# Speccy2007_128K_Ljubitel.net
KiCad netlist of a schematic drawn in EAGLE
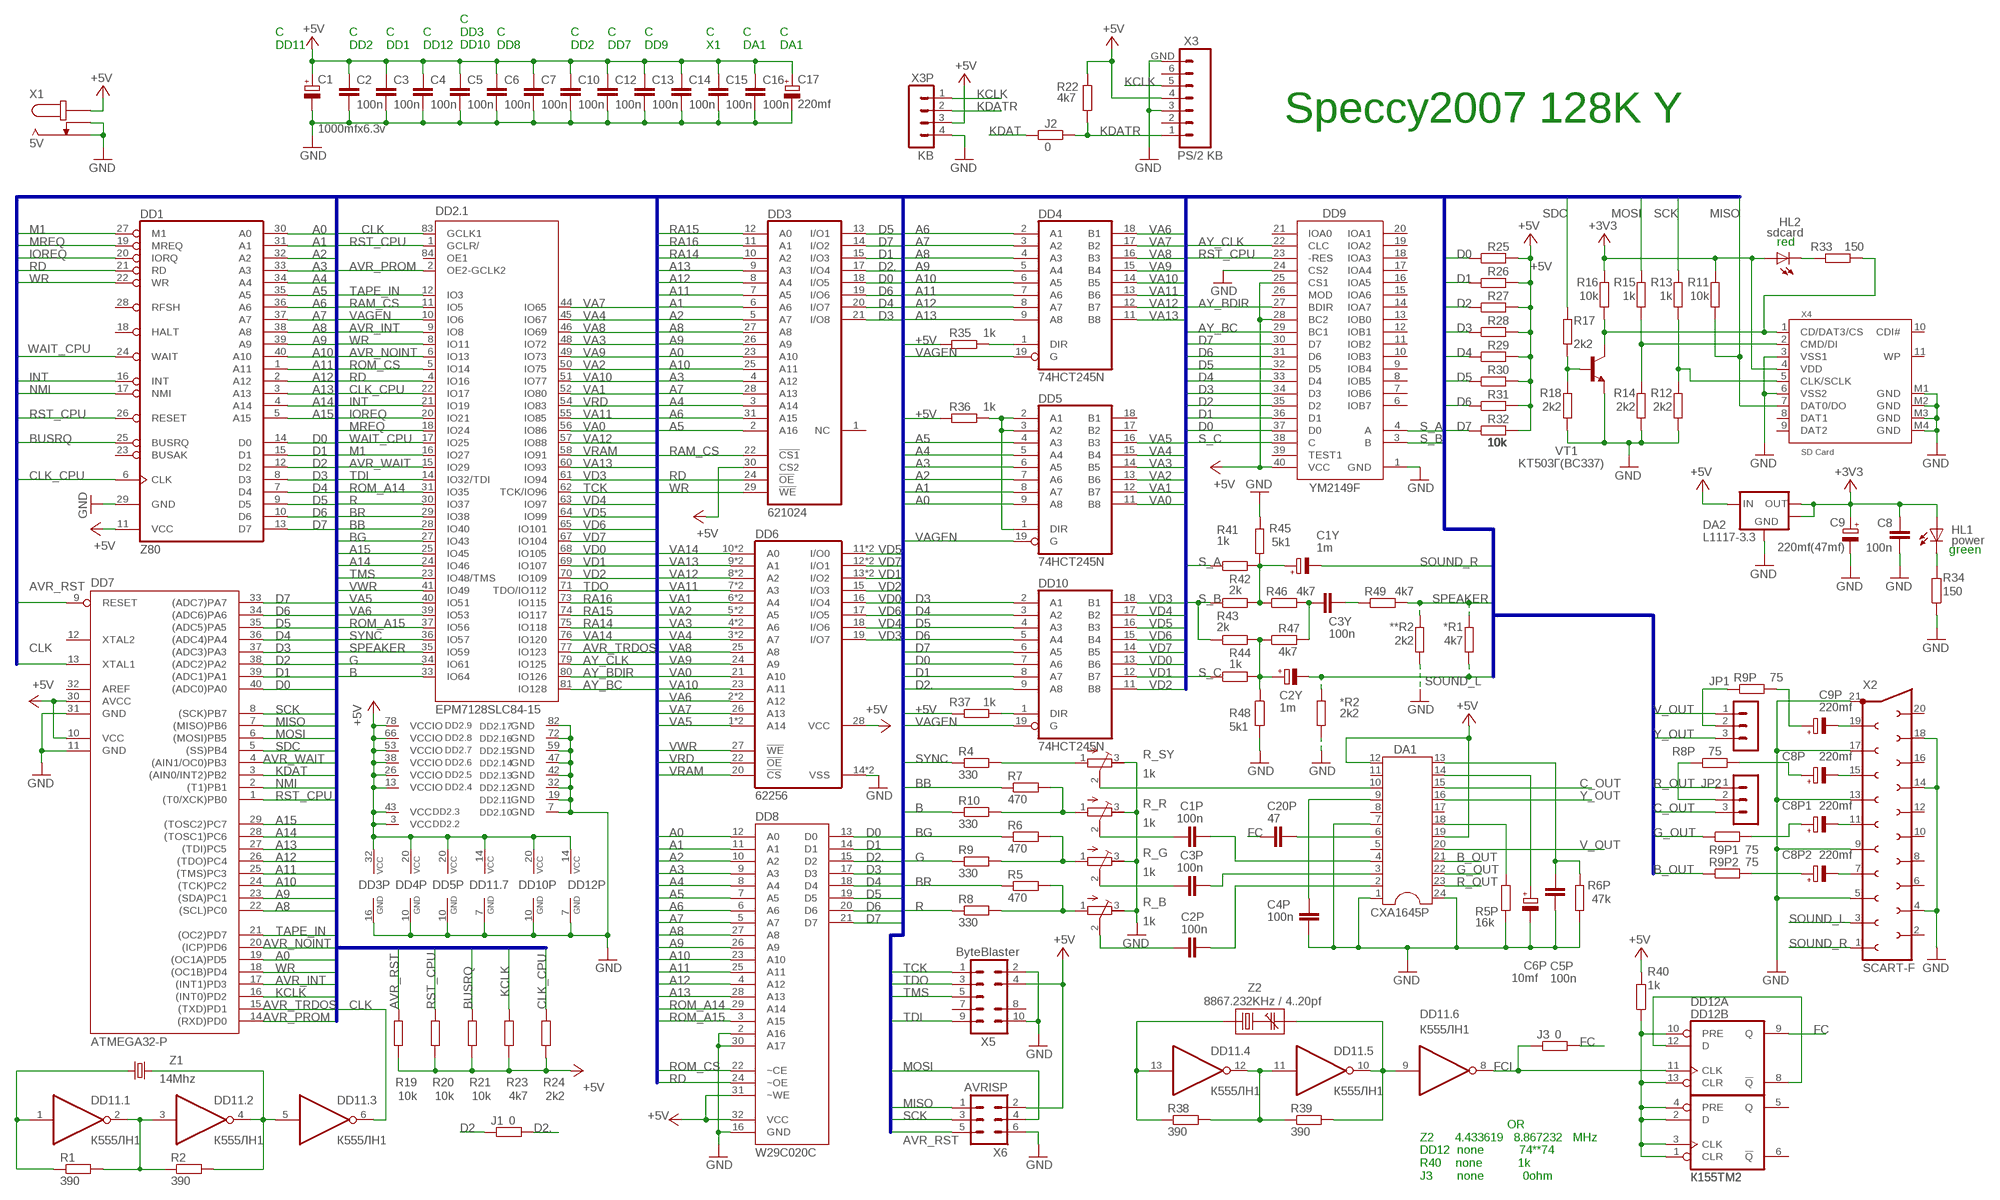
[diagram p0: schematic, sheet 1]

(export (version "E")
  (design (tool "Eeschema 10.0.6"))
  (components
    (comp (ref "**R2")
      (value "2k2")
      (footprint "eagle-import:R1206")
      (libsource (lib "eagle-import") (part "rcl_R-EU_R1206"))
    )
    (comp (ref "*R1")
      (value "4k7")
      (footprint "eagle-import:R0805")
      (libsource (lib "eagle-import") (part "rcl_R-EU_R0805"))
    )
    (comp (ref "*R2")
      (value "2k2")
      (footprint "eagle-import:R0805")
      (libsource (lib "eagle-import") (part "rcl_R-EU_R0805"))
    )
    (comp (ref "C1")
      (value "1000mfx6.3v")
      (footprint "eagle-import:E3,5-8")
      (libsource (lib "eagle-import") (part "CPOL-EUE3.5-8"))
    )
    (comp (ref "C1P")
      (value "100n")
      (footprint "eagle-import:C0805")
      (libsource (lib "eagle-import") (part "C-EUC0805"))
    )
    (comp (ref "C1Y")
      (value "1m")
      (footprint "eagle-import:E2,5-5")
      (libsource (lib "eagle-import") (part "CPOL-EUE2.5-5"))
    )
    (comp (ref "C2")
      (value "100n")
      (footprint "eagle-import:C0805")
      (libsource (lib "eagle-import") (part "C-EUC0805"))
    )
    (comp (ref "C2P")
      (value "100n")
      (footprint "eagle-import:C0805")
      (libsource (lib "eagle-import") (part "C-EUC0805"))
    )
    (comp (ref "C2Y")
      (value "1m")
      (footprint "eagle-import:E2,5-5")
      (libsource (lib "eagle-import") (part "CPOL-EUE2.5-5"))
    )
    (comp (ref "C3")
      (value "100n")
      (footprint "eagle-import:C0805")
      (libsource (lib "eagle-import") (part "C-EUC0805"))
    )
    (comp (ref "C3P")
      (value "100n")
      (footprint "eagle-import:C0805")
      (libsource (lib "eagle-import") (part "C-EUC0805"))
    )
    (comp (ref "C3Y")
      (value "100n")
      (footprint "eagle-import:C0805")
      (libsource (lib "eagle-import") (part "C-EUC0805"))
    )
    (comp (ref "C4")
      (value "100n")
      (footprint "eagle-import:C1206")
      (libsource (lib "eagle-import") (part "C-EUC1206"))
    )
    (comp (ref "C4P")
      (value "100n")
      (footprint "eagle-import:C0805")
      (libsource (lib "eagle-import") (part "C-EUC0805"))
    )
    (comp (ref "C5")
      (value "100n")
      (footprint "eagle-import:C0805")
      (libsource (lib "eagle-import") (part "C-EUC0805"))
    )
    (comp (ref "C5P")
      (value "100n")
      (footprint "eagle-import:C1206")
      (libsource (lib "eagle-import") (part "C-EUC1206"))
    )
    (comp (ref "C6")
      (value "100n")
      (footprint "eagle-import:C1206")
      (libsource (lib "eagle-import") (part "C-EUC1206"))
    )
    (comp (ref "C6P")
      (value "10mf")
      (footprint "eagle-import:E2,5-5")
      (libsource (lib "eagle-import") (part "CPOL-EUE2.5-5"))
    )
    (comp (ref "C7")
      (value "100n")
      (footprint "eagle-import:C0805")
      (libsource (lib "eagle-import") (part "C-EUC0805"))
    )
    (comp (ref "C8")
      (value "100n")
      (footprint "eagle-import:C0805")
      (libsource (lib "eagle-import") (part "C-EUC0805"))
    )
    (comp (ref "C8P")
      (value "220mf")
      (footprint "eagle-import:E2,5-6")
      (libsource (lib "eagle-import") (part "CPOL-EUE2.5-6"))
    )
    (comp (ref "C8P1")
      (value "220mf")
      (footprint "eagle-import:E2,5-6")
      (libsource (lib "eagle-import") (part "CPOL-EUE2.5-6"))
    )
    (comp (ref "C8P2")
      (value "220mf")
      (footprint "eagle-import:E2,5-6")
      (libsource (lib "eagle-import") (part "CPOL-EUE2.5-6"))
    )
    (comp (ref "C9")
      (value "220mf(47mf)")
      (footprint "eagle-import:E2,5-6")
      (libsource (lib "eagle-import") (part "CPOL-EUE2.5-6"))
    )
    (comp (ref "C9P")
      (value "220mf")
      (footprint "eagle-import:E2,5-6")
      (libsource (lib "eagle-import") (part "CPOL-EUE2.5-6"))
    )
    (comp (ref "C10")
      (value "100n")
      (footprint "eagle-import:C0805")
      (libsource (lib "eagle-import") (part "C-EUC0805"))
    )
    (comp (ref "C12")
      (value "100n")
      (footprint "eagle-import:C0805")
      (libsource (lib "eagle-import") (part "C-EUC0805"))
    )
    (comp (ref "C13")
      (value "100n")
      (footprint "eagle-import:C0805")
      (libsource (lib "eagle-import") (part "C-EUC0805"))
    )
    (comp (ref "C14")
      (value "100n")
      (footprint "eagle-import:C0805")
      (libsource (lib "eagle-import") (part "C-EUC0805"))
    )
    (comp (ref "C15")
      (value "100n")
      (footprint "eagle-import:C0805")
      (libsource (lib "eagle-import") (part "C-EUC0805"))
    )
    (comp (ref "C16")
      (value "100n")
      (footprint "eagle-import:C0805")
      (libsource (lib "eagle-import") (part "C-EUC0805"))
    )
    (comp (ref "C17")
      (value "220mf")
      (footprint "eagle-import:E2,5-6")
      (libsource (lib "eagle-import") (part "CPOL-EUE2.5-6"))
    )
    (comp (ref "C20P")
      (value "47")
      (footprint "eagle-import:C0805")
      (libsource (lib "eagle-import") (part "C-EUC0805"))
    )
    (comp (ref "DA1")
      (value "CXA1645P")
      (footprint "eagle-import:DIL24-4")
      (libsource (lib "eagle-import") (part "CXA1645-P"))
    )
    (comp (ref "DA2")
      (value "L1117-3.3")
      (footprint "eagle-import:SOT-223")
      (libsource (lib "eagle-import") (part "AP1117"))
    )
    (comp (ref "DD1")
      (value "Z80")
      (footprint "eagle-import:DIL40")
      (libsource (lib "eagle-import") (part "Z80CPU"))
    )
    (comp (ref "DD2")
      (value "EPM7128SLC84-15")
      (footprint "eagle-import:PGA-84-B")
      (libsource (lib "eagle-import") (part "EPM7128-J84"))
    )
    (comp (ref "DD3")
      (value "621024")
      (footprint "eagle-import:DIL32")
      (libsource (lib "eagle-import") (part "621024P"))
    )
    (comp (ref "DD4")
      (value "74HCT245N")
      (footprint "eagle-import:DIL20")
      (libsource (lib "eagle-import") (part "74245NHC"))
    )
    (comp (ref "DD5")
      (value "74HCT245N")
      (footprint "eagle-import:DIL20")
      (libsource (lib "eagle-import") (part "74245NHC"))
    )
    (comp (ref "DD6")
      (value "62256")
      (footprint "eagle-import:DIL28+6")
      (libsource (lib "eagle-import") (part "62256P+"))
    )
    (comp (ref "DD7")
      (value "ATMEGA32-P")
      (footprint "eagle-import:DIL40")
      (fields (field (name "MPN") "ATMEGA16-16PU"))
      (libsource (lib "eagle-import") (part "MEGA16-P"))
    )
    (comp (ref "DD8")
      (value "W29C020C")
      (footprint "eagle-import:DIL32")
      (libsource (lib "eagle-import") (part "W29C020C"))
    )
    (comp (ref "DD9")
      (value "YM2149F")
      (footprint "eagle-import:DIL40")
      (libsource (lib "eagle-import") (part "YM2149F"))
    )
    (comp (ref "DD10")
      (value "74HCT245N")
      (footprint "eagle-import:DIL20")
      (libsource (lib "eagle-import") (part "74245NHC"))
    )
    (comp (ref "DD11")
      (value "К555ЛН1")
      (footprint "eagle-import:DIL14")
      (libsource (lib "eagle-import") (part "7404NLS"))
    )
    (comp (ref "DD12")
      (value "К155ТМ2")
      (footprint "eagle-import:DIL14O")
      (libsource (lib "eagle-import") (part "7474OLS"))
    )
    (comp (ref "HL1")
      (value "power")
      (footprint "eagle-import:SML0805")
      (libsource (lib "eagle-import") (part "LEDSML0805"))
    )
    (comp (ref "HL2")
      (value "sdcard")
      (footprint "eagle-import:SML0805")
      (libsource (lib "eagle-import") (part "LEDSML0805"))
    )
    (comp (ref "J1")
      (value "0")
      (footprint "eagle-import:M1206")
      (libsource (lib "eagle-import") (part "rcl_R-EU_M1206"))
    )
    (comp (ref "J2")
      (value "0")
      (footprint "eagle-import:R1206")
      (libsource (lib "eagle-import") (part "rcl_R-EU_R1206"))
    )
    (comp (ref "J3")
      (value "0")
      (footprint "eagle-import:R0805")
      (libsource (lib "eagle-import") (part "rcl_R-EU_R0805"))
    )
    (comp (ref "JP1")
      (value "MA03-1")
      (footprint "eagle-import:MA03-1")
      (libsource (lib "eagle-import") (part "MA03-1"))
    )
    (comp (ref "JP2")
      (value "MA03-1")
      (footprint "eagle-import:MA03-1")
      (fields (field (name "OC_FARNELL") "unknown") (field (name "OC_NEWARK") "unknown"))
      (libsource (lib "eagle-import") (part "MA03-1"))
    )
    (comp (ref "R1")
      (value "390")
      (footprint "eagle-import:R0805")
      (libsource (lib "eagle-import") (part "rcl_R-EU_R0805"))
    )
    (comp (ref "R2")
      (value "390")
      (footprint "eagle-import:R0805")
      (libsource (lib "eagle-import") (part "rcl_R-EU_R0805"))
    )
    (comp (ref "R4")
      (value "330")
      (footprint "eagle-import:R0805")
      (libsource (lib "eagle-import") (part "rcl_R-EU_R0805"))
    )
    (comp (ref "R5")
      (value "470")
      (footprint "eagle-import:R0805")
      (libsource (lib "eagle-import") (part "rcl_R-EU_R0805"))
    )
    (comp (ref "R5P")
      (value "16k")
      (footprint "eagle-import:M1206")
      (libsource (lib "eagle-import") (part "rcl_R-EU_M1206"))
    )
    (comp (ref "R6")
      (value "470")
      (footprint "eagle-import:R1206")
      (libsource (lib "eagle-import") (part "rcl_R-EU_R1206"))
    )
    (comp (ref "R6P")
      (value "47k")
      (footprint "eagle-import:R0805")
      (libsource (lib "eagle-import") (part "rcl_R-EU_R0805"))
    )
    (comp (ref "R7")
      (value "470")
      (footprint "eagle-import:0207_10")
      (libsource (lib "eagle-import") (part "R-EU_0207/10"))
    )
    (comp (ref "R8")
      (value "330")
      (footprint "eagle-import:R0805")
      (libsource (lib "eagle-import") (part "rcl_R-EU_R0805"))
    )
    (comp (ref "R8P")
      (value "75")
      (footprint "eagle-import:R1206")
      (libsource (lib "eagle-import") (part "rcl_R-EU_R1206"))
    )
    (comp (ref "R9")
      (value "330")
      (footprint "eagle-import:R0805")
      (libsource (lib "eagle-import") (part "rcl_R-EU_R0805"))
    )
    (comp (ref "R9P")
      (value "75")
      (footprint "eagle-import:R1206")
      (libsource (lib "eagle-import") (part "rcl_R-EU_R1206"))
    )
    (comp (ref "R9P1")
      (value "75")
      (footprint "eagle-import:R1206")
      (libsource (lib "eagle-import") (part "rcl_R-EU_R1206"))
    )
    (comp (ref "R9P2")
      (value "75")
      (footprint "eagle-import:R1206")
      (libsource (lib "eagle-import") (part "rcl_R-EU_R1206"))
    )
    (comp (ref "R10")
      (value "330")
      (footprint "eagle-import:R0805")
      (libsource (lib "eagle-import") (part "rcl_R-EU_R0805"))
    )
    (comp (ref "R11")
      (value "10k")
      (footprint "eagle-import:R0805")
      (libsource (lib "eagle-import") (part "rcl_R-EU_R0805"))
    )
    (comp (ref "R12")
      (value "2k2")
      (footprint "eagle-import:R1206")
      (libsource (lib "eagle-import") (part "rcl_R-EU_R1206"))
    )
    (comp (ref "R13")
      (value "1k")
      (footprint "eagle-import:R0805")
      (libsource (lib "eagle-import") (part "rcl_R-EU_R0805"))
    )
    (comp (ref "R14")
      (value "2k2")
      (footprint "eagle-import:R0805")
      (libsource (lib "eagle-import") (part "rcl_R-EU_R0805"))
    )
    (comp (ref "R15")
      (value "1k")
      (footprint "eagle-import:R0805")
      (libsource (lib "eagle-import") (part "rcl_R-EU_R0805"))
    )
    (comp (ref "R16")
      (value "10k")
      (footprint "eagle-import:R0805")
      (libsource (lib "eagle-import") (part "rcl_R-EU_R0805"))
    )
    (comp (ref "R17")
      (value "2k2")
      (footprint "eagle-import:R0805")
      (libsource (lib "eagle-import") (part "rcl_R-EU_R0805"))
    )
    (comp (ref "R18")
      (value "2k2")
      (footprint "eagle-import:R0805")
      (libsource (lib "eagle-import") (part "rcl_R-EU_R0805"))
    )
    (comp (ref "R19")
      (value "10k")
      (footprint "eagle-import:M0805")
      (libsource (lib "eagle-import") (part "rcl_R-EU_M0805"))
    )
    (comp (ref "R20")
      (value "10k")
      (footprint "eagle-import:R0805")
      (libsource (lib "eagle-import") (part "rcl_R-EU_R0805"))
    )
    (comp (ref "R21")
      (value "10k")
      (footprint "eagle-import:0207_10")
      (libsource (lib "eagle-import") (part "R-EU_0207/10"))
    )
    (comp (ref "R22")
      (value "4k7")
      (footprint "eagle-import:R0805")
      (libsource (lib "eagle-import") (part "rcl_R-EU_R0805"))
    )
    (comp (ref "R23")
      (value "4k7")
      (footprint "eagle-import:R1206")
      (libsource (lib "eagle-import") (part "rcl_R-EU_R1206"))
    )
    (comp (ref "R24")
      (value "2k2")
      (footprint "eagle-import:0207_10")
      (libsource (lib "eagle-import") (part "R-EU_0207/10"))
    )
    (comp (ref "R25")
      (value "10k")
      (footprint "eagle-import:R0805")
      (libsource (lib "eagle-import") (part "rcl_R-EU_R0805"))
    )
    (comp (ref "R26")
      (value "10k")
      (footprint "eagle-import:M0805")
      (libsource (lib "eagle-import") (part "rcl_R-EU_M0805"))
    )
    (comp (ref "R27")
      (value "10k")
      (footprint "eagle-import:R0805")
      (libsource (lib "eagle-import") (part "rcl_R-EU_R0805"))
    )
    (comp (ref "R28")
      (value "10k")
      (footprint "eagle-import:R0805")
      (libsource (lib "eagle-import") (part "rcl_R-EU_R0805"))
    )
    (comp (ref "R29")
      (value "10k")
      (footprint "eagle-import:R0805")
      (libsource (lib "eagle-import") (part "rcl_R-EU_R0805"))
    )
    (comp (ref "R30")
      (value "10k")
      (footprint "eagle-import:R0805")
      (libsource (lib "eagle-import") (part "rcl_R-EU_R0805"))
    )
    (comp (ref "R31")
      (value "10k")
      (footprint "eagle-import:R0805")
      (libsource (lib "eagle-import") (part "rcl_R-EU_R0805"))
    )
    (comp (ref "R32")
      (value "10k")
      (footprint "eagle-import:R0805")
      (libsource (lib "eagle-import") (part "rcl_R-EU_R0805"))
    )
    (comp (ref "R33")
      (value "150")
      (footprint "eagle-import:R1206")
      (libsource (lib "eagle-import") (part "rcl_R-EU_R1206"))
    )
    (comp (ref "R34")
      (value "150")
      (footprint "eagle-import:R0805")
      (libsource (lib "eagle-import") (part "rcl_R-EU_R0805"))
    )
    (comp (ref "R35")
      (value "1k")
      (footprint "eagle-import:R0805")
      (libsource (lib "eagle-import") (part "rcl_R-EU_R0805"))
    )
    (comp (ref "R36")
      (value "1k")
      (footprint "eagle-import:R0805")
      (libsource (lib "eagle-import") (part "rcl_R-EU_R0805"))
    )
    (comp (ref "R37")
      (value "1k")
      (footprint "eagle-import:R0805")
      (libsource (lib "eagle-import") (part "rcl_R-EU_R0805"))
    )
    (comp (ref "R38")
      (value "390")
      (footprint "eagle-import:R0805")
      (libsource (lib "eagle-import") (part "rcl_R-EU_R0805"))
    )
    (comp (ref "R39")
      (value "390")
      (footprint "eagle-import:R0805")
      (libsource (lib "eagle-import") (part "rcl_R-EU_R0805"))
    )
    (comp (ref "R40")
      (value "1k")
      (footprint "eagle-import:R0805")
      (libsource (lib "eagle-import") (part "rcl_R-EU_R0805"))
    )
    (comp (ref "R41")
      (value "1k")
      (footprint "eagle-import:R0805")
      (libsource (lib "eagle-import") (part "rcl_R-EU_R0805"))
    )
    (comp (ref "R42")
      (value "2k")
      (footprint "eagle-import:R0805")
      (libsource (lib "eagle-import") (part "rcl_R-EU_R0805"))
    )
    (comp (ref "R43")
      (value "2k")
      (footprint "eagle-import:R1206")
      (libsource (lib "eagle-import") (part "rcl_R-EU_R1206"))
    )
    (comp (ref "R44")
      (value "1k")
      (footprint "eagle-import:R1206")
      (libsource (lib "eagle-import") (part "rcl_R-EU_R1206"))
    )
    (comp (ref "R45")
      (value "5k1")
      (footprint "eagle-import:R1206")
      (libsource (lib "eagle-import") (part "rcl_R-EU_R1206"))
    )
    (comp (ref "R46")
      (value "4k7")
      (footprint "eagle-import:R1206")
      (libsource (lib "eagle-import") (part "rcl_R-EU_R1206"))
    )
    (comp (ref "R47")
      (value "4k7")
      (footprint "eagle-import:R0805")
      (libsource (lib "eagle-import") (part "rcl_R-EU_R0805"))
    )
    (comp (ref "R48")
      (value "5k1")
      (footprint "eagle-import:R0805")
      (libsource (lib "eagle-import") (part "rcl_R-EU_R0805"))
    )
    (comp (ref "R49")
      (value "4k7")
      (footprint "eagle-import:R0805")
      (libsource (lib "eagle-import") (part "rcl_R-EU_R0805"))
    )
    (comp (ref "R_B")
      (value "1k")
      (footprint "eagle-import:RTRIM3296W")
      (libsource (lib "eagle-import") (part "R-TRIMM3296W"))
    )
    (comp (ref "R_G")
      (value "1k")
      (footprint "eagle-import:RTRIM3296W")
      (libsource (lib "eagle-import") (part "R-TRIMM3296W"))
    )
    (comp (ref "R_R")
      (value "1k")
      (footprint "eagle-import:RTRIM3296W")
      (libsource (lib "eagle-import") (part "R-TRIMM3296W"))
    )
    (comp (ref "R_SY")
      (value "1k")
      (footprint "eagle-import:RTRIM3296W")
      (libsource (lib "eagle-import") (part "R-TRIMM3296W"))
    )
    (comp (ref "VT1")
      (value "KT503Г(BC337)")
      (footprint "eagle-import:TO92-CBE")
      (libsource (lib "eagle-import") (part "-NPN-TO92-CBEBC550"))
    )
    (comp (ref "X1")
      (value "5V")
      (footprint "eagle-import:POWER3.5")
      (libsource (lib "eagle-import") (part "POWER3.5"))
    )
    (comp (ref "X2")
      (value "SCART-F")
      (footprint "eagle-import:SCART-F")
      (libsource (lib "eagle-import") (part "SCART-F"))
    )
    (comp (ref "X3")
      (value "PS/2 KB")
      (footprint "eagle-import:MINI-DIN6")
      (libsource (lib "eagle-import") (part "MINI-DIN6PTH"))
    )
    (comp (ref "X3P")
      (value "KB")
      (footprint "eagle-import:MA04-1")
      (libsource (lib "eagle-import") (part "MA04-1"))
    )
    (comp (ref "X4")
      (value "SD Card")
      (footprint "eagle-import:SDCMF-10915W010")
      (libsource (lib "eagle-import") (part "SDCARD"))
    )
    (comp (ref "X5")
      (value "ByteBlaster")
      (footprint "eagle-import:MA05-2")
      (libsource (lib "eagle-import") (part "MA05-2"))
    )
    (comp (ref "X6")
      (value "AVRISP")
      (footprint "eagle-import:MA03-2")
      (libsource (lib "eagle-import") (part "MA03-2"))
    )
    (comp (ref "Z1")
      (value "14Mhz")
      (footprint "eagle-import:HC49U-H")
      (libsource (lib "eagle-import") (part "CRYSTALHC49U-H"))
    )
    (comp (ref "Z2")
      (value "8867.232KHz / 4..20pf")
      (footprint "eagle-import:HC49U-H")
      (libsource (lib "eagle-import") (part "ZC"))
    )
  )
  (nets
    (net (code "1") (name "+3V3") (class "Default")
      (node (ref "C8") (pin "1") (pinfunction "1_1") (pintype "passive"))
      (node (ref "C9") (pin "+") (pinfunction "+_+") (pintype "passive"))
      (node (ref "DA2") (pin "2") (pinfunction "OUT_2") (pintype "power_in"))
      (node (ref "DA2") (pin "4") (pinfunction "OUT'_4") (pintype "power_in"))
      (node (ref "HL1") (pin "A") (pinfunction "A_A") (pintype "passive"))
      (node (ref "HL2") (pin "A") (pinfunction "A_A") (pintype "passive"))
      (node (ref "R11") (pin "2") (pinfunction "2_2") (pintype "passive"))
      (node (ref "R16") (pin "2") (pinfunction "2_2") (pintype "passive"))
      (node (ref "X4") (pin "4") (pinfunction "VDD_4") (pintype "power_in"))
    )
    (net (code "2") (name "+5V") (class "Default")
      (node (ref "C1") (pin "+") (pinfunction "+_+") (pintype "passive"))
      (node (ref "C10") (pin "1") (pinfunction "1_1") (pintype "passive"))
      (node (ref "C12") (pin "1") (pinfunction "1_1") (pintype "passive"))
      (node (ref "C13") (pin "1") (pinfunction "1_1") (pintype "passive"))
      (node (ref "C14") (pin "1") (pinfunction "1_1") (pintype "passive"))
      (node (ref "C15") (pin "1") (pinfunction "1_1") (pintype "passive"))
      (node (ref "C16") (pin "1") (pinfunction "1_1") (pintype "passive"))
      (node (ref "C17") (pin "+") (pinfunction "+_+") (pintype "passive"))
      (node (ref "C2") (pin "1") (pinfunction "1_1") (pintype "passive"))
      (node (ref "C3") (pin "1") (pinfunction "1_1") (pintype "passive"))
      (node (ref "C4") (pin "1") (pinfunction "1_1") (pintype "passive"))
      (node (ref "C5") (pin "1") (pinfunction "1_1") (pintype "passive"))
      (node (ref "C6") (pin "1") (pinfunction "1_1") (pintype "passive"))
      (node (ref "C7") (pin "1") (pinfunction "1_1") (pintype "passive"))
      (node (ref "DA1") (pin "12") (pinfunction "12_12") (pintype "passive"))
      (node (ref "DA1") (pin "19") (pinfunction "19_19") (pintype "passive"))
      (node (ref "DA2") (pin "3") (pinfunction "IN_3") (pintype "power_in"))
      (node (ref "DD1") (pin "11") (pinfunction "VCC_11") (pintype "power_in"))
      (node (ref "DD10") (pin "20") (pinfunction "VCC_20") (pintype "power_in"))
      (node (ref "DD11") (pin "14") (pinfunction "VCC_14") (pintype "power_in"))
      (node (ref "DD12") (pin "14") (pinfunction "VCC_14") (pintype "power_in"))
      (node (ref "DD2") (pin "13") (pinfunction "VCCIO_13") (pintype "power_in"))
      (node (ref "DD2") (pin "26") (pinfunction "VCCIO_26") (pintype "power_in"))
      (node (ref "DD2") (pin "3") (pinfunction "VCC_3") (pintype "power_in"))
      (node (ref "DD2") (pin "38") (pinfunction "VCCIO_38") (pintype "power_in"))
      (node (ref "DD2") (pin "43") (pinfunction "VCC_43") (pintype "power_in"))
      (node (ref "DD2") (pin "53") (pinfunction "VCCIO_53") (pintype "power_in"))
      (node (ref "DD2") (pin "66") (pinfunction "VCCIO_66") (pintype "power_in"))
      (node (ref "DD2") (pin "78") (pinfunction "VCCIO_78") (pintype "power_in"))
      (node (ref "DD3") (pin "30") (pinfunction "CS2_30") (pintype "input"))
      (node (ref "DD3") (pin "32") (pinfunction "VCC_32") (pintype "power_in"))
      (node (ref "DD4") (pin "20") (pinfunction "VCC_20") (pintype "power_in"))
      (node (ref "DD5") (pin "20") (pinfunction "VCC_20") (pintype "power_in"))
      (node (ref "DD6") (pin "28") (pinfunction "VCC_28") (pintype "power_in"))
      (node (ref "DD7") (pin "10") (pinfunction "VCC_10") (pintype "power_in"))
      (node (ref "DD7") (pin "30") (pinfunction "AVCC_30") (pintype "power_in"))
      (node (ref "DD8") (pin "31") (pinfunction "~{WE}_31") (pintype "input"))
      (node (ref "DD8") (pin "32") (pinfunction "VCC_32") (pintype "power_in"))
      (node (ref "DD9") (pin "25") (pinfunction "CS1_25") (pintype "bidirectional"))
      (node (ref "DD9") (pin "28") (pinfunction "BC2_28") (pintype "bidirectional"))
      (node (ref "DD9") (pin "40") (pinfunction "VCC_40") (pintype "bidirectional"))
      (node (ref "R19") (pin "1") (pinfunction "1_1") (pintype "passive"))
      (node (ref "R20") (pin "1") (pinfunction "1_1") (pintype "passive"))
      (node (ref "R21") (pin "1") (pinfunction "1_1") (pintype "passive"))
      (node (ref "R22") (pin "2") (pinfunction "2_2") (pintype "passive"))
      (node (ref "R23") (pin "1") (pinfunction "1_1") (pintype "passive"))
      (node (ref "R24") (pin "1") (pinfunction "1_1") (pintype "passive"))
      (node (ref "R25") (pin "2") (pinfunction "2_2") (pintype "passive"))
      (node (ref "R26") (pin "2") (pinfunction "2_2") (pintype "passive"))
      (node (ref "R27") (pin "2") (pinfunction "2_2") (pintype "passive"))
      (node (ref "R28") (pin "2") (pinfunction "2_2") (pintype "passive"))
      (node (ref "R29") (pin "2") (pinfunction "2_2") (pintype "passive"))
      (node (ref "R30") (pin "2") (pinfunction "2_2") (pintype "passive"))
      (node (ref "R31") (pin "2") (pinfunction "2_2") (pintype "passive"))
      (node (ref "R32") (pin "2") (pinfunction "2_2") (pintype "passive"))
      (node (ref "R35") (pin "2") (pinfunction "2_2") (pintype "passive"))
      (node (ref "R36") (pin "2") (pinfunction "2_2") (pintype "passive"))
      (node (ref "R37") (pin "2") (pinfunction "2_2") (pintype "passive"))
      (node (ref "R40") (pin "2") (pinfunction "2_2") (pintype "passive"))
      (node (ref "X1") (pin "P$1") (pinfunction "1_P$1") (pintype "passive"))
      (node (ref "X3") (pin "4") (pinfunction "4_4") (pintype "passive"))
      (node (ref "X3P") (pin "3") (pinfunction "3_3") (pintype "passive"))
      (node (ref "X5") (pin "4") (pinfunction "4_4") (pintype "passive"))
      (node (ref "X6") (pin "2") (pinfunction "2_2") (pintype "passive"))
    )
    (net (code "3") (name "/A0") (class "Default")
      (node (ref "DD1") (pin "30") (pinfunction "A0_30") (pintype "output"))
      (node (ref "DD3") (pin "23") (pinfunction "A10_23") (pintype "input"))
      (node (ref "DD5") (pin "9") (pinfunction "A8_9") (pintype "bidirectional"))
      (node (ref "DD7") (pin "19") (pinfunction "(OC1A)PD5_19") (pintype "bidirectional"))
      (node (ref "DD8") (pin "12") (pinfunction "A0_12") (pintype "input"))
    )
    (net (code "4") (name "/A1") (class "Default")
      (node (ref "DD1") (pin "31") (pinfunction "A1_31") (pintype "output"))
      (node (ref "DD3") (pin "6") (pinfunction "A6_6") (pintype "input"))
      (node (ref "DD5") (pin "8") (pinfunction "A7_8") (pintype "bidirectional"))
      (node (ref "DD8") (pin "11") (pinfunction "A1_11") (pintype "input"))
    )
    (net (code "5") (name "/A2") (class "Default")
      (node (ref "DD1") (pin "32") (pinfunction "A2_32") (pintype "output"))
      (node (ref "DD3") (pin "5") (pinfunction "A7_5") (pintype "input"))
      (node (ref "DD5") (pin "7") (pinfunction "A6_7") (pintype "bidirectional"))
      (node (ref "DD8") (pin "10") (pinfunction "A2_10") (pintype "input"))
    )
    (net (code "6") (name "/A3") (class "Default")
      (node (ref "DD1") (pin "33") (pinfunction "A3_33") (pintype "output"))
      (node (ref "DD3") (pin "4") (pinfunction "A12_4") (pintype "input"))
      (node (ref "DD5") (pin "6") (pinfunction "A5_6") (pintype "bidirectional"))
      (node (ref "DD8") (pin "9") (pinfunction "A3_9") (pintype "input"))
    )
    (net (code "7") (name "/A4") (class "Default")
      (node (ref "DD1") (pin "34") (pinfunction "A4_34") (pintype "output"))
      (node (ref "DD3") (pin "3") (pinfunction "A14_3") (pintype "input"))
      (node (ref "DD5") (pin "5") (pinfunction "A4_5") (pintype "bidirectional"))
      (node (ref "DD8") (pin "8") (pinfunction "A4_8") (pintype "input"))
    )
    (net (code "8") (name "/A5") (class "Default")
      (node (ref "DD1") (pin "35") (pinfunction "A5_35") (pintype "output"))
      (node (ref "DD3") (pin "2") (pinfunction "A16_2") (pintype "input"))
      (node (ref "DD5") (pin "4") (pinfunction "A3_4") (pintype "bidirectional"))
      (node (ref "DD8") (pin "7") (pinfunction "A5_7") (pintype "input"))
    )
    (net (code "9") (name "/A6") (class "Default")
      (node (ref "DD1") (pin "36") (pinfunction "A6_36") (pintype "output"))
      (node (ref "DD3") (pin "31") (pinfunction "A15_31") (pintype "input"))
      (node (ref "DD4") (pin "2") (pinfunction "A1_2") (pintype "bidirectional"))
      (node (ref "DD8") (pin "6") (pinfunction "A6_6") (pintype "input"))
    )
    (net (code "10") (name "/A7") (class "Default")
      (node (ref "DD1") (pin "37") (pinfunction "A7_37") (pintype "output"))
      (node (ref "DD3") (pin "28") (pinfunction "A13_28") (pintype "input"))
      (node (ref "DD4") (pin "3") (pinfunction "A2_3") (pintype "bidirectional"))
      (node (ref "DD8") (pin "5") (pinfunction "A7_5") (pintype "input"))
    )
    (net (code "11") (name "/A8") (class "Default")
      (node (ref "DD1") (pin "38") (pinfunction "A8_38") (pintype "output"))
      (node (ref "DD3") (pin "27") (pinfunction "A8_27") (pintype "input"))
      (node (ref "DD4") (pin "4") (pinfunction "A3_4") (pintype "bidirectional"))
      (node (ref "DD7") (pin "22") (pinfunction "(SCL)PC0_22") (pintype "bidirectional"))
      (node (ref "DD8") (pin "27") (pinfunction "A8_27") (pintype "input"))
    )
    (net (code "12") (name "/A9") (class "Default")
      (node (ref "DD1") (pin "39") (pinfunction "A9_39") (pintype "output"))
      (node (ref "DD3") (pin "26") (pinfunction "A9_26") (pintype "input"))
      (node (ref "DD4") (pin "5") (pinfunction "A4_5") (pintype "bidirectional"))
      (node (ref "DD7") (pin "23") (pinfunction "(SDA)PC1_23") (pintype "bidirectional"))
      (node (ref "DD8") (pin "26") (pinfunction "A9_26") (pintype "input"))
    )
    (net (code "13") (name "/A10") (class "Default")
      (node (ref "DD1") (pin "40") (pinfunction "A10_40") (pintype "output"))
      (node (ref "DD3") (pin "25") (pinfunction "A11_25") (pintype "input"))
      (node (ref "DD4") (pin "6") (pinfunction "A5_6") (pintype "bidirectional"))
      (node (ref "DD7") (pin "24") (pinfunction "(TCK)PC2_24") (pintype "bidirectional"))
      (node (ref "DD8") (pin "23") (pinfunction "A10_23") (pintype "input"))
    )
    (net (code "14") (name "/A11") (class "Default")
      (node (ref "DD1") (pin "1") (pinfunction "A11_1") (pintype "output"))
      (node (ref "DD3") (pin "7") (pinfunction "A5_7") (pintype "input"))
      (node (ref "DD4") (pin "7") (pinfunction "A6_7") (pintype "bidirectional"))
      (node (ref "DD7") (pin "25") (pinfunction "(TMS)PC3_25") (pintype "bidirectional"))
      (node (ref "DD8") (pin "25") (pinfunction "A11_25") (pintype "input"))
    )
    (net (code "15") (name "/A12") (class "Default")
      (node (ref "DD1") (pin "2") (pinfunction "A12_2") (pintype "output"))
      (node (ref "DD3") (pin "8") (pinfunction "A4_8") (pintype "input"))
      (node (ref "DD4") (pin "8") (pinfunction "A7_8") (pintype "bidirectional"))
      (node (ref "DD7") (pin "26") (pinfunction "(TDO)PC4_26") (pintype "bidirectional"))
      (node (ref "DD8") (pin "4") (pinfunction "A12_4") (pintype "input"))
    )
    (net (code "16") (name "/A13") (class "Default")
      (node (ref "DD1") (pin "3") (pinfunction "A13_3") (pintype "output"))
      (node (ref "DD3") (pin "9") (pinfunction "A3_9") (pintype "input"))
      (node (ref "DD4") (pin "9") (pinfunction "A8_9") (pintype "bidirectional"))
      (node (ref "DD7") (pin "27") (pinfunction "(TDI)PC5_27") (pintype "bidirectional"))
      (node (ref "DD8") (pin "28") (pinfunction "A13_28") (pintype "input"))
    )
    (net (code "17") (name "/A14") (class "Default")
      (node (ref "DD1") (pin "4") (pinfunction "A14_4") (pintype "output"))
      (node (ref "DD2") (pin "24") (pinfunction "IO46_24") (pintype "bidirectional"))
      (node (ref "DD7") (pin "28") (pinfunction "(TOSC1)PC6_28") (pintype "bidirectional"))
    )
    (net (code "18") (name "/A15") (class "Default")
      (node (ref "DD1") (pin "5") (pinfunction "A15_5") (pintype "output"))
      (node (ref "DD2") (pin "25") (pinfunction "IO45_25") (pintype "bidirectional"))
      (node (ref "DD7") (pin "29") (pinfunction "(TOSC2)PC7_29") (pintype "bidirectional"))
    )
    (net (code "19") (name "/AVR_INT") (class "Default")
      (node (ref "DD2") (pin "9") (pinfunction "IO8_9") (pintype "bidirectional"))
      (node (ref "DD7") (pin "17") (pinfunction "(INT1)PD3_17") (pintype "bidirectional"))
    )
    (net (code "20") (name "/AVR_NOINT") (class "Default")
      (node (ref "DD2") (pin "6") (pinfunction "IO13_6") (pintype "bidirectional"))
      (node (ref "DD7") (pin "20") (pinfunction "(ICP)PD6_20") (pintype "bidirectional"))
    )
    (net (code "21") (name "/AVR_PROM") (class "Default")
      (node (ref "DD2") (pin "2") (pinfunction "OE2-GCLK2_2") (pintype "input"))
      (node (ref "DD7") (pin "14") (pinfunction "(RXD)PD0_14") (pintype "bidirectional"))
    )
    (net (code "22") (name "/AVR_RST") (class "Default")
      (node (ref "DD7") (pin "9") (pinfunction "RESET_9") (pintype "input"))
      (node (ref "R19") (pin "2") (pinfunction "2_2") (pintype "passive"))
      (node (ref "X6") (pin "5") (pinfunction "5_5") (pintype "passive"))
    )
    (net (code "23") (name "/AVR_TRDOS") (class "Default")
      (node (ref "DD2") (pin "77") (pinfunction "IO123_77") (pintype "bidirectional"))
      (node (ref "DD7") (pin "15") (pinfunction "(TXD)PD1_15") (pintype "bidirectional"))
    )
    (net (code "24") (name "/AVR_WAIT") (class "Default")
      (node (ref "DD2") (pin "15") (pinfunction "IO29_15") (pintype "bidirectional"))
      (node (ref "DD7") (pin "4") (pinfunction "(AIN1/OC0)PB3_4") (pintype "bidirectional"))
    )
    (net (code "25") (name "/AY_BC") (class "Default")
      (node (ref "DD2") (pin "81") (pinfunction "IO128_81") (pintype "bidirectional"))
      (node (ref "DD9") (pin "29") (pinfunction "BC1_29") (pintype "bidirectional"))
    )
    (net (code "26") (name "/AY_BDIR") (class "Default")
      (node (ref "DD2") (pin "80") (pinfunction "IO126_80") (pintype "bidirectional"))
      (node (ref "DD9") (pin "27") (pinfunction "BDIR_27") (pintype "bidirectional"))
    )
    (net (code "27") (name "/AY_CLK") (class "Default")
      (node (ref "DD2") (pin "79") (pinfunction "IO125_79") (pintype "bidirectional"))
      (node (ref "DD9") (pin "22") (pinfunction "CLC_22") (pintype "bidirectional"))
    )
    (net (code "28") (name "/B") (class "Default")
      (node (ref "DD2") (pin "33") (pinfunction "IO64_33") (pintype "bidirectional"))
      (node (ref "R10") (pin "1") (pinfunction "1_1") (pintype "passive"))
    )
    (net (code "29") (name "/BB") (class "Default")
      (node (ref "DD2") (pin "28") (pinfunction "IO40_28") (pintype "bidirectional"))
      (node (ref "R7") (pin "1") (pinfunction "1_1") (pintype "passive"))
    )
    (net (code "30") (name "/BG") (class "Default")
      (node (ref "DD2") (pin "27") (pinfunction "IO43_27") (pintype "bidirectional"))
      (node (ref "R6") (pin "1") (pinfunction "1_1") (pintype "passive"))
    )
    (net (code "31") (name "/BR") (class "Default")
      (node (ref "DD2") (pin "29") (pinfunction "IO38_29") (pintype "bidirectional"))
      (node (ref "R5") (pin "1") (pinfunction "1_1") (pintype "passive"))
    )
    (net (code "32") (name "/BUSRQ") (class "Default")
      (node (ref "DD1") (pin "25") (pinfunction "BUSRQ_25") (pintype "input"))
      (node (ref "R21") (pin "2") (pinfunction "2_2") (pintype "passive"))
    )
    (net (code "33") (name "/B_OUT") (class "Default")
      (node (ref "DA1") (pin "21") (pinfunction "21_21") (pintype "passive"))
      (node (ref "R9P2") (pin "1") (pinfunction "1_1") (pintype "passive"))
    )
    (net (code "34") (name "/CLK") (class "Default")
      (node (ref "DD11") (pin "6") (pinfunction "O_6") (pintype "output"))
      (node (ref "DD2") (pin "83") (pinfunction "GCLK1_83") (pintype "input"))
      (node (ref "DD7") (pin "13") (pinfunction "XTAL1_13") (pintype "bidirectional"))
    )
    (net (code "35") (name "/CLK_CPU") (class "Default")
      (node (ref "DD1") (pin "6") (pinfunction "CLK_6") (pintype "input"))
      (node (ref "DD2") (pin "22") (pinfunction "IO17_22") (pintype "bidirectional"))
      (node (ref "R24") (pin "2") (pinfunction "2_2") (pintype "passive"))
    )
    (net (code "36") (name "/C_OUT") (class "Default")
      (node (ref "DA1") (pin "15") (pinfunction "15_15") (pintype "passive"))
      (node (ref "JP2") (pin "3") (pinfunction "3_3") (pintype "passive"))
    )
    (net (code "37") (name "/D0") (class "Default")
      (node (ref "DD1") (pin "14") (pinfunction "D0_14") (pintype "bidirectional"))
      (node (ref "DD10") (pin "7") (pinfunction "A6_7") (pintype "bidirectional"))
      (node (ref "DD3") (pin "18") (pinfunction "I/O5_18") (pintype "bidirectional"))
      (node (ref "DD7") (pin "40") (pinfunction "(ADC0)PA0_40") (pintype "bidirectional"))
      (node (ref "DD8") (pin "13") (pinfunction "D0_13") (pintype "bidirectional"))
      (node (ref "DD9") (pin "37") (pinfunction "D0_37") (pintype "bidirectional"))
      (node (ref "R25") (pin "1") (pinfunction "1_1") (pintype "passive"))
    )
    (net (code "38") (name "/D1") (class "Default")
      (node (ref "DD1") (pin "15") (pinfunction "D1_15") (pintype "bidirectional"))
      (node (ref "DD10") (pin "8") (pinfunction "A7_8") (pintype "bidirectional"))
      (node (ref "DD3") (pin "15") (pinfunction "I/O3_15") (pintype "bidirectional"))
      (node (ref "DD7") (pin "39") (pinfunction "(ADC1)PA1_39") (pintype "bidirectional"))
      (node (ref "DD8") (pin "14") (pinfunction "D1_14") (pintype "bidirectional"))
      (node (ref "DD9") (pin "36") (pinfunction "D1_36") (pintype "bidirectional"))
      (node (ref "R26") (pin "1") (pinfunction "1_1") (pintype "passive"))
    )
    (net (code "39") (name "/D2") (class "Default")
      (node (ref "DD1") (pin "12") (pinfunction "D2_12") (pintype "bidirectional"))
      (node (ref "DD7") (pin "38") (pinfunction "(ADC2)PA2_38") (pintype "bidirectional"))
      (node (ref "DD9") (pin "35") (pinfunction "D2_35") (pintype "bidirectional"))
      (node (ref "J1") (pin "1") (pinfunction "1_1") (pintype "passive"))
      (node (ref "R27") (pin "1") (pinfunction "1_1") (pintype "passive"))
    )
    (net (code "40") (name "/D2.") (class "Default")
      (node (ref "DD10") (pin "9") (pinfunction "A8_9") (pintype "bidirectional"))
      (node (ref "DD3") (pin "17") (pinfunction "I/O4_17") (pintype "bidirectional"))
      (node (ref "DD8") (pin "15") (pinfunction "D2_15") (pintype "bidirectional"))
      (node (ref "J1") (pin "2") (pinfunction "2_2") (pintype "passive"))
    )
    (net (code "41") (name "/D3") (class "Default")
      (node (ref "DD1") (pin "8") (pinfunction "D3_8") (pintype "bidirectional"))
      (node (ref "DD10") (pin "2") (pinfunction "A1_2") (pintype "bidirectional"))
      (node (ref "DD3") (pin "21") (pinfunction "I/O8_21") (pintype "bidirectional"))
      (node (ref "DD7") (pin "37") (pinfunction "(ADC3)PA3_37") (pintype "bidirectional"))
      (node (ref "DD8") (pin "17") (pinfunction "D3_17") (pintype "bidirectional"))
      (node (ref "DD9") (pin "34") (pinfunction "D3_34") (pintype "bidirectional"))
      (node (ref "R28") (pin "1") (pinfunction "1_1") (pintype "passive"))
    )
    (net (code "42") (name "/D4") (class "Default")
      (node (ref "DD1") (pin "7") (pinfunction "D4_7") (pintype "bidirectional"))
      (node (ref "DD10") (pin "3") (pinfunction "A2_3") (pintype "bidirectional"))
      (node (ref "DD3") (pin "20") (pinfunction "I/O7_20") (pintype "bidirectional"))
      (node (ref "DD7") (pin "36") (pinfunction "(ADC4)PA4_36") (pintype "bidirectional"))
      (node (ref "DD8") (pin "18") (pinfunction "D4_18") (pintype "bidirectional"))
      (node (ref "DD9") (pin "33") (pinfunction "D4_33") (pintype "bidirectional"))
      (node (ref "R29") (pin "1") (pinfunction "1_1") (pintype "passive"))
    )
    (net (code "43") (name "/D5") (class "Default")
      (node (ref "DD1") (pin "9") (pinfunction "D5_9") (pintype "bidirectional"))
      (node (ref "DD10") (pin "4") (pinfunction "A3_4") (pintype "bidirectional"))
      (node (ref "DD3") (pin "13") (pinfunction "I/O1_13") (pintype "bidirectional"))
      (node (ref "DD7") (pin "35") (pinfunction "(ADC5)PA5_35") (pintype "bidirectional"))
      (node (ref "DD8") (pin "19") (pinfunction "D5_19") (pintype "bidirectional"))
      (node (ref "DD9") (pin "32") (pinfunction "D5_32") (pintype "bidirectional"))
      (node (ref "R30") (pin "1") (pinfunction "1_1") (pintype "passive"))
    )
    (net (code "44") (name "/D6") (class "Default")
      (node (ref "DD1") (pin "10") (pinfunction "D6_10") (pintype "bidirectional"))
      (node (ref "DD10") (pin "5") (pinfunction "A4_5") (pintype "bidirectional"))
      (node (ref "DD3") (pin "19") (pinfunction "I/O6_19") (pintype "bidirectional"))
      (node (ref "DD7") (pin "34") (pinfunction "(ADC6)PA6_34") (pintype "bidirectional"))
      (node (ref "DD8") (pin "20") (pinfunction "D6_20") (pintype "bidirectional"))
      (node (ref "DD9") (pin "31") (pinfunction "D6_31") (pintype "bidirectional"))
      (node (ref "R31") (pin "1") (pinfunction "1_1") (pintype "passive"))
    )
    (net (code "45") (name "/D7") (class "Default")
      (node (ref "DD1") (pin "13") (pinfunction "D7_13") (pintype "bidirectional"))
      (node (ref "DD10") (pin "6") (pinfunction "A5_6") (pintype "bidirectional"))
      (node (ref "DD3") (pin "14") (pinfunction "I/O2_14") (pintype "bidirectional"))
      (node (ref "DD7") (pin "33") (pinfunction "(ADC7)PA7_33") (pintype "bidirectional"))
      (node (ref "DD8") (pin "21") (pinfunction "D7_21") (pintype "bidirectional"))
      (node (ref "DD9") (pin "30") (pinfunction "D7_30") (pintype "bidirectional"))
      (node (ref "R32") (pin "1") (pinfunction "1_1") (pintype "passive"))
    )
    (net (code "46") (name "/FC") (class "Default")
      (node (ref "C20P") (pin "1") (pinfunction "1_1") (pintype "passive"))
      (node (ref "DD12") (pin "9") (pinfunction "Q_9") (pintype "output"))
      (node (ref "J3") (pin "2") (pinfunction "2_2") (pintype "passive"))
    )
    (net (code "47") (name "/FCI") (class "Default")
      (node (ref "DD11") (pin "8") (pinfunction "O_8") (pintype "output"))
      (node (ref "DD12") (pin "11") (pinfunction "CLK_11") (pintype "input"))
      (node (ref "J3") (pin "1") (pinfunction "1_1") (pintype "passive"))
    )
    (net (code "48") (name "/G") (class "Default")
      (node (ref "DD2") (pin "34") (pinfunction "IO61_34") (pintype "bidirectional"))
      (node (ref "R9") (pin "1") (pinfunction "1_1") (pintype "passive"))
    )
    (net (code "49") (name "/G_OUT") (class "Default")
      (node (ref "DA1") (pin "22") (pinfunction "22_22") (pintype "passive"))
      (node (ref "R9P1") (pin "1") (pinfunction "1_1") (pintype "passive"))
    )
    (net (code "50") (name "/INT") (class "Default")
      (node (ref "DD1") (pin "16") (pinfunction "INT_16") (pintype "input"))
      (node (ref "DD2") (pin "21") (pinfunction "IO19_21") (pintype "bidirectional"))
    )
    (net (code "51") (name "/IOREQ") (class "Default")
      (node (ref "DD1") (pin "20") (pinfunction "IORQ_20") (pintype "output"))
      (node (ref "DD2") (pin "20") (pinfunction "IO21_20") (pintype "bidirectional"))
    )
    (net (code "52") (name "/KCLK") (class "Default")
      (node (ref "DD7") (pin "16") (pinfunction "(INT0)PD2_16") (pintype "bidirectional"))
      (node (ref "R23") (pin "2") (pinfunction "2_2") (pintype "passive"))
      (node (ref "X3") (pin "5") (pinfunction "5_5") (pintype "passive"))
      (node (ref "X3P") (pin "1") (pinfunction "1_1") (pintype "passive"))
    )
    (net (code "53") (name "/KDAT") (class "Default")
      (node (ref "DD7") (pin "3") (pinfunction "(AIN0/INT2)PB2_3") (pintype "bidirectional"))
      (node (ref "J2") (pin "1") (pinfunction "1_1") (pintype "passive"))
    )
    (net (code "54") (name "/KDATR") (class "Default")
      (node (ref "J2") (pin "2") (pinfunction "2_2") (pintype "passive"))
      (node (ref "R22") (pin "1") (pinfunction "1_1") (pintype "passive"))
      (node (ref "X3") (pin "1") (pinfunction "1_1") (pintype "passive"))
      (node (ref "X3P") (pin "2") (pinfunction "2_2") (pintype "passive"))
    )
    (net (code "55") (name "/M1") (class "Default")
      (node (ref "DD1") (pin "27") (pinfunction "M1_27") (pintype "output"))
      (node (ref "DD2") (pin "16") (pinfunction "IO27_16") (pintype "bidirectional"))
    )
    (net (code "56") (name "/MISO") (class "Default")
      (node (ref "DD7") (pin "7") (pinfunction "(MISO)PB6_7") (pintype "bidirectional"))
      (node (ref "R11") (pin "1") (pinfunction "1_1") (pintype "passive"))
      (node (ref "X4") (pin "7") (pinfunction "DAT0/DO_7") (pintype "bidirectional"))
      (node (ref "X6") (pin "1") (pinfunction "1_1") (pintype "passive"))
    )
    (net (code "57") (name "/MOSI") (class "Default")
      (node (ref "DD7") (pin "6") (pinfunction "(MOSI)PB5_6") (pintype "bidirectional"))
      (node (ref "R15") (pin "2") (pinfunction "2_2") (pintype "passive"))
      (node (ref "X6") (pin "4") (pinfunction "4_4") (pintype "passive"))
    )
    (net (code "58") (name "/MREQ") (class "Default")
      (node (ref "DD1") (pin "19") (pinfunction "MREQ_19") (pintype "output"))
      (node (ref "DD2") (pin "18") (pinfunction "IO24_18") (pintype "bidirectional"))
    )
    (net (code "59") (name "/NMI") (class "Default")
      (node (ref "DD1") (pin "17") (pinfunction "NMI_17") (pintype "input"))
      (node (ref "DD7") (pin "2") (pinfunction "(T1)PB1_2") (pintype "bidirectional"))
    )
    (net (code "60") (name "/R") (class "Default")
      (node (ref "DD2") (pin "30") (pinfunction "IO37_30") (pintype "bidirectional"))
      (node (ref "R8") (pin "1") (pinfunction "1_1") (pintype "passive"))
    )
    (net (code "61") (name "/RA14") (class "Default")
      (node (ref "DD2") (pin "75") (pinfunction "IO118_75") (pintype "bidirectional"))
      (node (ref "DD3") (pin "10") (pinfunction "A2_10") (pintype "input"))
    )
    (net (code "62") (name "/RA15") (class "Default")
      (node (ref "DD2") (pin "74") (pinfunction "IO117_74") (pintype "bidirectional"))
      (node (ref "DD3") (pin "12") (pinfunction "A0_12") (pintype "input"))
    )
    (net (code "63") (name "/RA16") (class "Default")
      (node (ref "DD2") (pin "73") (pinfunction "IO115_73") (pintype "bidirectional"))
      (node (ref "DD3") (pin "11") (pinfunction "A1_11") (pintype "input"))
    )
    (net (code "64") (name "/RAM_CS") (class "Default")
      (node (ref "DD2") (pin "11") (pinfunction "IO5_11") (pintype "bidirectional"))
      (node (ref "DD3") (pin "22") (pinfunction "~{CS1}_22") (pintype "input"))
    )
    (net (code "65") (name "/RD") (class "Default")
      (node (ref "DD1") (pin "21") (pinfunction "RD_21") (pintype "output"))
      (node (ref "DD2") (pin "4") (pinfunction "IO16_4") (pintype "bidirectional"))
      (node (ref "DD3") (pin "24") (pinfunction "~{OE}_24") (pintype "input"))
      (node (ref "DD8") (pin "24") (pinfunction "~{OE}_24") (pintype "input"))
    )
    (net (code "66") (name "/ROM_A14") (class "Default")
      (node (ref "DD2") (pin "31") (pinfunction "IO35_31") (pintype "bidirectional"))
      (node (ref "DD8") (pin "29") (pinfunction "A14_29") (pintype "input"))
    )
    (net (code "67") (name "/ROM_A15") (class "Default")
      (node (ref "DD2") (pin "37") (pinfunction "IO56_37") (pintype "bidirectional"))
      (node (ref "DD8") (pin "3") (pinfunction "A15_3") (pintype "input"))
    )
    (net (code "68") (name "/ROM_CS") (class "Default")
      (node (ref "DD2") (pin "5") (pinfunction "IO14_5") (pintype "bidirectional"))
      (node (ref "DD8") (pin "22") (pinfunction "~{CE}_22") (pintype "input"))
    )
    (net (code "69") (name "/RST_CPU") (class "Default")
      (node (ref "DD1") (pin "26") (pinfunction "RESET_26") (pintype "input"))
      (node (ref "DD2") (pin "1") (pinfunction "GCLR/_1") (pintype "input"))
      (node (ref "DD7") (pin "1") (pinfunction "(T0/XCK)PB0_1") (pintype "bidirectional"))
      (node (ref "DD9") (pin "23") (pinfunction "-RES_23") (pintype "bidirectional"))
      (node (ref "R20") (pin "2") (pinfunction "2_2") (pintype "passive"))
    )
    (net (code "70") (name "/R_OUT") (class "Default")
      (node (ref "DA1") (pin "23") (pinfunction "23_23") (pintype "passive"))
      (node (ref "JP2") (pin "1") (pinfunction "1_1") (pintype "passive"))
    )
    (net (code "71") (name "/SCK") (class "Default")
      (node (ref "DD7") (pin "8") (pinfunction "(SCK)PB7_8") (pintype "bidirectional"))
      (node (ref "R13") (pin "2") (pinfunction "2_2") (pintype "passive"))
      (node (ref "X6") (pin "3") (pinfunction "3_3") (pintype "passive"))
    )
    (net (code "72") (name "/SDC") (class "Default")
      (node (ref "DD7") (pin "5") (pinfunction "(SS)PB4_5") (pintype "bidirectional"))
      (node (ref "R17") (pin "2") (pinfunction "2_2") (pintype "passive"))
    )
    (net (code "73") (name "/SOUND_L") (class "Default")
      (node (ref "*R1") (pin "1") (pinfunction "1_1") (pintype "passive"))
      (node (ref "*R2") (pin "2") (pinfunction "2_2") (pintype "passive"))
      (node (ref "C2Y") (pin "-") (pinfunction "-_-") (pintype "passive"))
      (node (ref "X2") (pin "3") (pinfunction "3_3") (pintype "passive"))
    )
    (net (code "74") (name "/SOUND_R") (class "Default")
      (node (ref "C1Y") (pin "-") (pinfunction "-_-") (pintype "passive"))
      (node (ref "X2") (pin "1") (pinfunction "1_1") (pintype "passive"))
    )
    (net (code "75") (name "/SPEAKER") (class "Default")
      (node (ref "**R2") (pin "2") (pinfunction "2_2") (pintype "passive"))
      (node (ref "*R1") (pin "2") (pinfunction "2_2") (pintype "passive"))
      (node (ref "DD2") (pin "35") (pinfunction "IO59_35") (pintype "bidirectional"))
      (node (ref "R49") (pin "2") (pinfunction "2_2") (pintype "passive"))
    )
    (net (code "76") (name "/SYNC") (class "Default")
      (node (ref "DD2") (pin "36") (pinfunction "IO57_36") (pintype "bidirectional"))
      (node (ref "R4") (pin "1") (pinfunction "1_1") (pintype "passive"))
    )
    (net (code "77") (name "/S_A") (class "Default")
      (node (ref "DD9") (pin "4") (pinfunction "A_4") (pintype "bidirectional"))
      (node (ref "R41") (pin "1") (pinfunction "1_1") (pintype "passive"))
    )
    (net (code "78") (name "/S_B") (class "Default")
      (node (ref "DD9") (pin "3") (pinfunction "B_3") (pintype "bidirectional"))
      (node (ref "R42") (pin "1") (pinfunction "1_1") (pintype "passive"))
      (node (ref "R43") (pin "1") (pinfunction "1_1") (pintype "passive"))
    )
    (net (code "79") (name "/S_C") (class "Default")
      (node (ref "DD9") (pin "38") (pinfunction "C_38") (pintype "bidirectional"))
      (node (ref "R44") (pin "1") (pinfunction "1_1") (pintype "passive"))
    )
    (net (code "80") (name "/TAPE_IN") (class "Default")
      (node (ref "DD2") (pin "12") (pinfunction "IO3_12") (pintype "bidirectional"))
      (node (ref "DD7") (pin "21") (pinfunction "(OC2)PD7_21") (pintype "bidirectional"))
    )
    (net (code "81") (name "/TCK") (class "Default")
      (node (ref "DD2") (pin "62") (pinfunction "TCK/IO96_62") (pintype "bidirectional"))
      (node (ref "X5") (pin "1") (pinfunction "1_1") (pintype "passive"))
    )
    (net (code "82") (name "/TDI") (class "Default")
      (node (ref "DD2") (pin "14") (pinfunction "IO32/TDI_14") (pintype "bidirectional"))
      (node (ref "X5") (pin "9") (pinfunction "9_9") (pintype "passive"))
    )
    (net (code "83") (name "/TDO") (class "Default")
      (node (ref "DD2") (pin "71") (pinfunction "TDO/IO112_71") (pintype "bidirectional"))
      (node (ref "X5") (pin "3") (pinfunction "3_3") (pintype "passive"))
    )
    (net (code "84") (name "/TMS") (class "Default")
      (node (ref "DD2") (pin "23") (pinfunction "IO48/TMS_23") (pintype "bidirectional"))
      (node (ref "X5") (pin "5") (pinfunction "5_5") (pintype "passive"))
    )
    (net (code "85") (name "/VA0") (class "Default")
      (node (ref "DD2") (pin "56") (pinfunction "IO86_56") (pintype "bidirectional"))
      (node (ref "DD5") (pin "11") (pinfunction "B8_11") (pintype "bidirectional"))
      (node (ref "DD6") (pin "21") (pinfunction "A10_21") (pintype "input"))
    )
    (net (code "86") (name "/VA1") (class "Default")
      (node (ref "DD2") (pin "52") (pinfunction "IO80_52") (pintype "bidirectional"))
      (node (ref "DD5") (pin "12") (pinfunction "B7_12") (pintype "bidirectional"))
      (node (ref "DD6") (pin "6") (pinfunction "A4_6") (pintype "input"))
      (node (ref "DD6") (pin "P$6") (pinfunction "A4_P$6") (pintype "input"))
    )
    (net (code "87") (name "/VA2") (class "Default")
      (node (ref "DD2") (pin "50") (pinfunction "IO75_50") (pintype "bidirectional"))
      (node (ref "DD5") (pin "13") (pinfunction "B6_13") (pintype "bidirectional"))
      (node (ref "DD6") (pin "5") (pinfunction "A5_5") (pintype "input"))
      (node (ref "DD6") (pin "P$5") (pinfunction "A5_P$5") (pintype "input"))
    )
    (net (code "88") (name "/VA3") (class "Default")
      (node (ref "DD2") (pin "48") (pinfunction "IO72_48") (pintype "bidirectional"))
      (node (ref "DD5") (pin "14") (pinfunction "B5_14") (pintype "bidirectional"))
      (node (ref "DD6") (pin "4") (pinfunction "A6_4") (pintype "input"))
      (node (ref "DD6") (pin "P$4") (pinfunction "A6_P$4") (pintype "input"))
    )
    (net (code "89") (name "/VA4") (class "Default")
      (node (ref "DD2") (pin "45") (pinfunction "IO67_45") (pintype "bidirectional"))
      (node (ref "DD5") (pin "15") (pinfunction "B4_15") (pintype "bidirectional"))
      (node (ref "DD6") (pin "3") (pinfunction "A7_3") (pintype "input"))
      (node (ref "DD6") (pin "P$3") (pinfunction "A7_P$3") (pintype "input"))
    )
    (net (code "90") (name "/VA5") (class "Default")
      (node (ref "DD2") (pin "40") (pinfunction "IO51_40") (pintype "bidirectional"))
      (node (ref "DD5") (pin "16") (pinfunction "B3_16") (pintype "bidirectional"))
      (node (ref "DD6") (pin "1") (pinfunction "A14_1") (pintype "input"))
      (node (ref "DD6") (pin "P$1") (pinfunction "A14_P$1") (pintype "input"))
    )
    (net (code "91") (name "/VA6") (class "Default")
      (node (ref "DD2") (pin "39") (pinfunction "IO53_39") (pintype "bidirectional"))
      (node (ref "DD4") (pin "18") (pinfunction "B1_18") (pintype "bidirectional"))
      (node (ref "DD6") (pin "2") (pinfunction "A12_2") (pintype "input"))
      (node (ref "DD6") (pin "P$2") (pinfunction "A12_P$2") (pintype "input"))
    )
    (net (code "92") (name "/VA7") (class "Default")
      (node (ref "DD2") (pin "44") (pinfunction "IO65_44") (pintype "bidirectional"))
      (node (ref "DD4") (pin "17") (pinfunction "B2_17") (pintype "bidirectional"))
      (node (ref "DD6") (pin "26") (pinfunction "A13_26") (pintype "input"))
    )
    (net (code "93") (name "/VA8") (class "Default")
      (node (ref "DD2") (pin "46") (pinfunction "IO69_46") (pintype "bidirectional"))
      (node (ref "DD4") (pin "16") (pinfunction "B3_16") (pintype "bidirectional"))
      (node (ref "DD6") (pin "25") (pinfunction "A8_25") (pintype "input"))
    )
    (net (code "94") (name "/VA9") (class "Default")
      (node (ref "DD2") (pin "49") (pinfunction "IO73_49") (pintype "bidirectional"))
      (node (ref "DD4") (pin "15") (pinfunction "B4_15") (pintype "bidirectional"))
      (node (ref "DD6") (pin "24") (pinfunction "A9_24") (pintype "input"))
    )
    (net (code "95") (name "/VA10") (class "Default")
      (node (ref "DD2") (pin "51") (pinfunction "IO77_51") (pintype "bidirectional"))
      (node (ref "DD4") (pin "14") (pinfunction "B5_14") (pintype "bidirectional"))
      (node (ref "DD6") (pin "23") (pinfunction "A11_23") (pintype "input"))
    )
    (net (code "96") (name "/VA11") (class "Default")
      (node (ref "DD2") (pin "55") (pinfunction "IO85_55") (pintype "bidirectional"))
      (node (ref "DD4") (pin "13") (pinfunction "B6_13") (pintype "bidirectional"))
      (node (ref "DD6") (pin "7") (pinfunction "A3_7") (pintype "input"))
      (node (ref "DD6") (pin "P$7") (pinfunction "A3_P$7") (pintype "input"))
    )
    (net (code "97") (name "/VA12") (class "Default")
      (node (ref "DD2") (pin "57") (pinfunction "IO88_57") (pintype "bidirectional"))
      (node (ref "DD4") (pin "12") (pinfunction "B7_12") (pintype "bidirectional"))
      (node (ref "DD6") (pin "8") (pinfunction "A2_8") (pintype "input"))
      (node (ref "DD6") (pin "P$8") (pinfunction "A2_P$8") (pintype "input"))
    )
    (net (code "98") (name "/VA13") (class "Default")
      (node (ref "DD2") (pin "60") (pinfunction "IO93_60") (pintype "bidirectional"))
      (node (ref "DD4") (pin "11") (pinfunction "B8_11") (pintype "bidirectional"))
      (node (ref "DD6") (pin "9") (pinfunction "A1_9") (pintype "input"))
      (node (ref "DD6") (pin "P$9") (pinfunction "A1_P$9") (pintype "input"))
    )
    (net (code "99") (name "/VA14") (class "Default")
      (node (ref "DD2") (pin "76") (pinfunction "IO120_76") (pintype "bidirectional"))
      (node (ref "DD6") (pin "10") (pinfunction "A0_10") (pintype "input"))
      (node (ref "DD6") (pin "P$10") (pinfunction "A0_P$10") (pintype "input"))
    )
    (net (code "100") (name "/VAGEN") (class "Default")
      (node (ref "DD10") (pin "19") (pinfunction "G_19") (pintype "input"))
      (node (ref "DD2") (pin "10") (pinfunction "IO6_10") (pintype "bidirectional"))
      (node (ref "DD4") (pin "19") (pinfunction "G_19") (pintype "input"))
      (node (ref "DD5") (pin "19") (pinfunction "G_19") (pintype "input"))
    )
    (net (code "101") (name "/VD0") (class "Default")
      (node (ref "DD10") (pin "13") (pinfunction "B6_13") (pintype "bidirectional"))
      (node (ref "DD2") (pin "68") (pinfunction "IO105_68") (pintype "bidirectional"))
      (node (ref "DD6") (pin "16") (pinfunction "I/O4_16") (pintype "bidirectional"))
    )
    (net (code "102") (name "/VD1") (class "Default")
      (node (ref "DD10") (pin "12") (pinfunction "B7_12") (pintype "bidirectional"))
      (node (ref "DD2") (pin "69") (pinfunction "IO107_69") (pintype "bidirectional"))
      (node (ref "DD6") (pin "13") (pinfunction "I/O2_13") (pintype "bidirectional"))
      (node (ref "DD6") (pin "P$13") (pinfunction "I/O2_P$13") (pintype "bidirectional"))
    )
    (net (code "103") (name "/VD2") (class "Default")
      (node (ref "DD10") (pin "11") (pinfunction "B8_11") (pintype "bidirectional"))
      (node (ref "DD2") (pin "70") (pinfunction "IO109_70") (pintype "bidirectional"))
      (node (ref "DD6") (pin "15") (pinfunction "I/O3_15") (pintype "bidirectional"))
    )
    (net (code "104") (name "/VD3") (class "Default")
      (node (ref "DD10") (pin "18") (pinfunction "B1_18") (pintype "bidirectional"))
      (node (ref "DD2") (pin "61") (pinfunction "IO94_61") (pintype "bidirectional"))
      (node (ref "DD6") (pin "19") (pinfunction "I/O7_19") (pintype "bidirectional"))
    )
    (net (code "105") (name "/VD4") (class "Default")
      (node (ref "DD10") (pin "17") (pinfunction "B2_17") (pintype "bidirectional"))
      (node (ref "DD2") (pin "63") (pinfunction "IO97_63") (pintype "bidirectional"))
      (node (ref "DD6") (pin "18") (pinfunction "I/O6_18") (pintype "bidirectional"))
    )
    (net (code "106") (name "/VD5") (class "Default")
      (node (ref "DD10") (pin "16") (pinfunction "B3_16") (pintype "bidirectional"))
      (node (ref "DD2") (pin "64") (pinfunction "IO99_64") (pintype "bidirectional"))
      (node (ref "DD6") (pin "11") (pinfunction "I/O0_11") (pintype "bidirectional"))
      (node (ref "DD6") (pin "P$11") (pinfunction "I/O0_P$11") (pintype "bidirectional"))
    )
    (net (code "107") (name "/VD6") (class "Default")
      (node (ref "DD10") (pin "15") (pinfunction "B4_15") (pintype "bidirectional"))
      (node (ref "DD2") (pin "65") (pinfunction "IO101_65") (pintype "bidirectional"))
      (node (ref "DD6") (pin "17") (pinfunction "I/O5_17") (pintype "bidirectional"))
    )
    (net (code "108") (name "/VD7") (class "Default")
      (node (ref "DD10") (pin "14") (pinfunction "B5_14") (pintype "bidirectional"))
      (node (ref "DD2") (pin "67") (pinfunction "IO104_67") (pintype "bidirectional"))
      (node (ref "DD6") (pin "12") (pinfunction "I/O1_12") (pintype "bidirectional"))
      (node (ref "DD6") (pin "P$12") (pinfunction "I/O1_P$12") (pintype "bidirectional"))
    )
    (net (code "109") (name "/VRAM") (class "Default")
      (node (ref "DD2") (pin "58") (pinfunction "IO91_58") (pintype "bidirectional"))
      (node (ref "DD6") (pin "20") (pinfunction "~{CS}_20") (pintype "input"))
    )
    (net (code "110") (name "/VRD") (class "Default")
      (node (ref "DD2") (pin "54") (pinfunction "IO83_54") (pintype "bidirectional"))
      (node (ref "DD6") (pin "22") (pinfunction "~{OE}_22") (pintype "input"))
    )
    (net (code "111") (name "/VWR") (class "Default")
      (node (ref "DD2") (pin "41") (pinfunction "IO49_41") (pintype "bidirectional"))
      (node (ref "DD6") (pin "27") (pinfunction "~{WE}_27") (pintype "input"))
    )
    (net (code "112") (name "/V_OUT") (class "Default")
      (node (ref "DA1") (pin "20") (pinfunction "20_20") (pintype "passive"))
      (node (ref "JP1") (pin "1") (pinfunction "1_1") (pintype "passive"))
    )
    (net (code "113") (name "/WAIT_CPU") (class "Default")
      (node (ref "DD1") (pin "24") (pinfunction "WAIT_24") (pintype "input"))
      (node (ref "DD2") (pin "17") (pinfunction "IO25_17") (pintype "bidirectional"))
    )
    (net (code "114") (name "/WR") (class "Default")
      (node (ref "DD1") (pin "22") (pinfunction "WR_22") (pintype "output"))
      (node (ref "DD2") (pin "8") (pinfunction "IO11_8") (pintype "bidirectional"))
      (node (ref "DD3") (pin "29") (pinfunction "~{WE}_29") (pintype "input"))
      (node (ref "DD7") (pin "18") (pinfunction "(OC1B)PD4_18") (pintype "bidirectional"))
    )
    (net (code "115") (name "/Y_OUT") (class "Default")
      (node (ref "DA1") (pin "16") (pinfunction "16_16") (pintype "passive"))
      (node (ref "JP1") (pin "3") (pinfunction "3_3") (pintype "passive"))
    )
    (net (code "116") (name "GND") (class "Default")
      (node (ref "**R2") (pin "1") (pinfunction "1_1") (pintype "passive"))
      (node (ref "*R2") (pin "1") (pinfunction "1_1") (pintype "passive"))
      (node (ref "C1") (pin "-") (pinfunction "-_-") (pintype "passive"))
      (node (ref "C10") (pin "2") (pinfunction "2_2") (pintype "passive"))
      (node (ref "C12") (pin "2") (pinfunction "2_2") (pintype "passive"))
      (node (ref "C13") (pin "2") (pinfunction "2_2") (pintype "passive"))
      (node (ref "C14") (pin "2") (pinfunction "2_2") (pintype "passive"))
      (node (ref "C15") (pin "2") (pinfunction "2_2") (pintype "passive"))
      (node (ref "C16") (pin "2") (pinfunction "2_2") (pintype "passive"))
      (node (ref "C17") (pin "-") (pinfunction "-_-") (pintype "passive"))
      (node (ref "C2") (pin "2") (pinfunction "2_2") (pintype "passive"))
      (node (ref "C3") (pin "2") (pinfunction "2_2") (pintype "passive"))
      (node (ref "C4") (pin "2") (pinfunction "2_2") (pintype "passive"))
      (node (ref "C4P") (pin "1") (pinfunction "1_1") (pintype "passive"))
      (node (ref "C5") (pin "2") (pinfunction "2_2") (pintype "passive"))
      (node (ref "C5P") (pin "1") (pinfunction "1_1") (pintype "passive"))
      (node (ref "C6") (pin "2") (pinfunction "2_2") (pintype "passive"))
      (node (ref "C6P") (pin "-") (pinfunction "-_-") (pintype "passive"))
      (node (ref "C7") (pin "2") (pinfunction "2_2") (pintype "passive"))
      (node (ref "C8") (pin "2") (pinfunction "2_2") (pintype "passive"))
      (node (ref "C9") (pin "-") (pinfunction "-_-") (pintype "passive"))
      (node (ref "DA1") (pin "1") (pinfunction "1_1") (pintype "passive"))
      (node (ref "DA1") (pin "24") (pinfunction "24_24") (pintype "passive"))
      (node (ref "DA1") (pin "7") (pinfunction "7_7") (pintype "passive"))
      (node (ref "DA2") (pin "1") (pinfunction "GND_1") (pintype "power_in"))
      (node (ref "DD1") (pin "29") (pinfunction "GND_29") (pintype "power_in"))
      (node (ref "DD10") (pin "10") (pinfunction "GND_10") (pintype "power_in"))
      (node (ref "DD11") (pin "7") (pinfunction "GND_7") (pintype "power_in"))
      (node (ref "DD12") (pin "7") (pinfunction "GND_7") (pintype "power_in"))
      (node (ref "DD2") (pin "19") (pinfunction "GND_19") (pintype "power_in"))
      (node (ref "DD2") (pin "32") (pinfunction "GND_32") (pintype "power_in"))
      (node (ref "DD2") (pin "42") (pinfunction "GND_42") (pintype "power_in"))
      (node (ref "DD2") (pin "47") (pinfunction "GND_47") (pintype "power_in"))
      (node (ref "DD2") (pin "59") (pinfunction "GND_59") (pintype "power_in"))
      (node (ref "DD2") (pin "7") (pinfunction "GND_7") (pintype "power_in"))
      (node (ref "DD2") (pin "72") (pinfunction "GND_72") (pintype "power_in"))
      (node (ref "DD2") (pin "82") (pinfunction "GND_82") (pintype "power_in"))
      (node (ref "DD3") (pin "16") (pinfunction "GND_16") (pintype "power_in"))
      (node (ref "DD4") (pin "10") (pinfunction "GND_10") (pintype "power_in"))
      (node (ref "DD5") (pin "10") (pinfunction "GND_10") (pintype "power_in"))
      (node (ref "DD6") (pin "14") (pinfunction "VSS_14") (pintype "power_in"))
      (node (ref "DD6") (pin "P$14") (pinfunction "VSS_P$14") (pintype "power_in"))
      (node (ref "DD7") (pin "11") (pinfunction "GND_11") (pintype "power_in"))
      (node (ref "DD7") (pin "31") (pinfunction "GND_31") (pintype "power_in"))
      (node (ref "DD8") (pin "16") (pinfunction "GND_16") (pintype "power_in"))
      (node (ref "DD8") (pin "2") (pinfunction "A16_2") (pintype "input"))
      (node (ref "DD8") (pin "30") (pinfunction "A17_30") (pintype "input"))
      (node (ref "DD9") (pin "1") (pinfunction "GND_1") (pintype "bidirectional"))
      (node (ref "DD9") (pin "24") (pinfunction "CS2_24") (pintype "bidirectional"))
      (node (ref "R12") (pin "1") (pinfunction "1_1") (pintype "passive"))
      (node (ref "R14") (pin "1") (pinfunction "1_1") (pintype "passive"))
      (node (ref "R18") (pin "1") (pinfunction "1_1") (pintype "passive"))
      (node (ref "R34") (pin "1") (pinfunction "1_1") (pintype "passive"))
      (node (ref "R45") (pin "2") (pinfunction "2_2") (pintype "passive"))
      (node (ref "R48") (pin "2") (pinfunction "2_2") (pintype "passive"))
      (node (ref "R5P") (pin "1") (pinfunction "1_1") (pintype "passive"))
      (node (ref "R6P") (pin "1") (pinfunction "1_1") (pintype "passive"))
      (node (ref "R_B") (pin "3") (pinfunction "A_3") (pintype "passive"))
      (node (ref "R_G") (pin "3") (pinfunction "A_3") (pintype "passive"))
      (node (ref "R_R") (pin "3") (pinfunction "A_3") (pintype "passive"))
      (node (ref "R_SY") (pin "3") (pinfunction "A_3") (pintype "passive"))
      (node (ref "VT1") (pin "E") (pinfunction "E_E") (pintype "passive"))
      (node (ref "X1") (pin "P$2") (pinfunction "2_P$2") (pintype "passive"))
      (node (ref "X1") (pin "P$3") (pinfunction "3_P$3") (pintype "passive"))
      (node (ref "X2") (pin "13") (pinfunction "13_13") (pintype "passive"))
      (node (ref "X2") (pin "14") (pinfunction "14_14") (pintype "passive"))
      (node (ref "X2") (pin "17") (pinfunction "17_17") (pintype "passive"))
      (node (ref "X2") (pin "18") (pinfunction "18_18") (pintype "passive"))
      (node (ref "X2") (pin "21") (pinfunction "21_21") (pintype "passive"))
      (node (ref "X2") (pin "4") (pinfunction "4_4") (pintype "passive"))
      (node (ref "X2") (pin "5") (pinfunction "5_5") (pintype "passive"))
      (node (ref "X2") (pin "9") (pinfunction "9_9") (pintype "passive"))
      (node (ref "X3") (pin "3") (pinfunction "3_3") (pintype "passive"))
      (node (ref "X3") (pin "GND") (pinfunction "7_GND") (pintype "passive"))
      (node (ref "X3P") (pin "4") (pinfunction "4_4") (pintype "passive"))
      (node (ref "X4") (pin "3") (pinfunction "VSS1_3") (pintype "power_in"))
      (node (ref "X4") (pin "6") (pinfunction "VSS2_6") (pintype "power_in"))
      (node (ref "X4") (pin "M1") (pinfunction "GND_M1") (pintype "power_in"))
      (node (ref "X4") (pin "M2") (pinfunction "GND_M2") (pintype "power_in"))
      (node (ref "X4") (pin "M3") (pinfunction "GND_M3") (pintype "power_in"))
      (node (ref "X4") (pin "M4") (pinfunction "GND_M4") (pintype "power_in"))
      (node (ref "X5") (pin "10") (pinfunction "10_10") (pintype "passive"))
      (node (ref "X5") (pin "2") (pinfunction "2_2") (pintype "passive"))
      (node (ref "X6") (pin "6") (pinfunction "6_6") (pintype "passive"))
    )
    (net (code "117") (name "Net-(C1P-Pad2)") (class "Default")
      (node (ref "C1P") (pin "2") (pinfunction "2_2") (pintype "passive"))
      (node (ref "DA1") (pin "4") (pinfunction "4_4") (pintype "passive"))
    )
    (net (code "118") (name "Net-(C1Y-Pad+)") (class "Default")
      (node (ref "C1Y") (pin "+") (pinfunction "+_+") (pintype "passive"))
      (node (ref "R41") (pin "2") (pinfunction "2_2") (pintype "passive"))
      (node (ref "R42") (pin "2") (pinfunction "2_2") (pintype "passive"))
      (node (ref "R45") (pin "1") (pinfunction "1_1") (pintype "passive"))
      (node (ref "R46") (pin "1") (pinfunction "1_1") (pintype "passive"))
    )
    (net (code "119") (name "Net-(C2P-Pad2)") (class "Default")
      (node (ref "C2P") (pin "2") (pinfunction "2_2") (pintype "passive"))
      (node (ref "DA1") (pin "2") (pinfunction "2_2") (pintype "passive"))
    )
    (net (code "120") (name "Net-(C2Y-Pad+)") (class "Default")
      (node (ref "C2Y") (pin "+") (pinfunction "+_+") (pintype "passive"))
      (node (ref "R43") (pin "2") (pinfunction "2_2") (pintype "passive"))
      (node (ref "R44") (pin "2") (pinfunction "2_2") (pintype "passive"))
      (node (ref "R47") (pin "1") (pinfunction "1_1") (pintype "passive"))
      (node (ref "R48") (pin "1") (pinfunction "1_1") (pintype "passive"))
    )
    (net (code "121") (name "Net-(C3P-Pad2)") (class "Default")
      (node (ref "C3P") (pin "2") (pinfunction "2_2") (pintype "passive"))
      (node (ref "DA1") (pin "3") (pinfunction "3_3") (pintype "passive"))
    )
    (net (code "122") (name "Net-(C3Y-Pad1)") (class "Default")
      (node (ref "C3Y") (pin "1") (pinfunction "1_1") (pintype "passive"))
      (node (ref "R46") (pin "2") (pinfunction "2_2") (pintype "passive"))
      (node (ref "R47") (pin "2") (pinfunction "2_2") (pintype "passive"))
    )
    (net (code "123") (name "Net-(C3Y-Pad2)") (class "Default")
      (node (ref "C3Y") (pin "2") (pinfunction "2_2") (pintype "passive"))
      (node (ref "R49") (pin "1") (pinfunction "1_1") (pintype "passive"))
    )
    (net (code "124") (name "Net-(C4P-Pad2)") (class "Default")
      (node (ref "C4P") (pin "2") (pinfunction "2_2") (pintype "passive"))
      (node (ref "DA1") (pin "9") (pinfunction "9_9") (pintype "passive"))
    )
    (net (code "125") (name "Net-(C5P-Pad2)") (class "Default")
      (node (ref "C5P") (pin "2") (pinfunction "2_2") (pintype "passive"))
      (node (ref "DA1") (pin "13") (pinfunction "13_13") (pintype "passive"))
      (node (ref "R6P") (pin "2") (pinfunction "2_2") (pintype "passive"))
    )
    (net (code "126") (name "Net-(C6P-Pad+)") (class "Default")
      (node (ref "C6P") (pin "+") (pinfunction "+_+") (pintype "passive"))
      (node (ref "DA1") (pin "14") (pinfunction "14_14") (pintype "passive"))
    )
    (net (code "127") (name "Net-(C8P-Pad+)") (class "Default")
      (node (ref "C8P") (pin "+") (pinfunction "+_+") (pintype "passive"))
      (node (ref "R8P") (pin "2") (pinfunction "2_2") (pintype "passive"))
    )
    (net (code "128") (name "Net-(C8P-Pad-)") (class "Default")
      (node (ref "C8P") (pin "-") (pinfunction "-_-") (pintype "passive"))
      (node (ref "X2") (pin "15") (pinfunction "15_15") (pintype "passive"))
    )
    (net (code "129") (name "Net-(C8P1-Pad+)") (class "Default")
      (node (ref "C8P1") (pin "+") (pinfunction "+_+") (pintype "passive"))
      (node (ref "R9P1") (pin "2") (pinfunction "2_2") (pintype "passive"))
    )
    (net (code "130") (name "Net-(C8P1-Pad-)") (class "Default")
      (node (ref "C8P1") (pin "-") (pinfunction "-_-") (pintype "passive"))
      (node (ref "X2") (pin "11") (pinfunction "11_11") (pintype "passive"))
    )
    (net (code "131") (name "Net-(C8P2-Pad+)") (class "Default")
      (node (ref "C8P2") (pin "+") (pinfunction "+_+") (pintype "passive"))
      (node (ref "R9P2") (pin "2") (pinfunction "2_2") (pintype "passive"))
    )
    (net (code "132") (name "Net-(C8P2-Pad-)") (class "Default")
      (node (ref "C8P2") (pin "-") (pinfunction "-_-") (pintype "passive"))
      (node (ref "X2") (pin "7") (pinfunction "7_7") (pintype "passive"))
    )
    (net (code "133") (name "Net-(C9P-Pad+)") (class "Default")
      (node (ref "C9P") (pin "+") (pinfunction "+_+") (pintype "passive"))
      (node (ref "R9P") (pin "2") (pinfunction "2_2") (pintype "passive"))
    )
    (net (code "134") (name "Net-(C9P-Pad-)") (class "Default")
      (node (ref "C9P") (pin "-") (pinfunction "-_-") (pintype "passive"))
      (node (ref "X2") (pin "19") (pinfunction "19_19") (pintype "passive"))
    )
    (net (code "135") (name "Net-(C20P-Pad2)") (class "Default")
      (node (ref "C20P") (pin "2") (pinfunction "2_2") (pintype "passive"))
      (node (ref "DA1") (pin "6") (pinfunction "6_6") (pintype "passive"))
    )
    (net (code "136") (name "Net-(DA1-Pad18)") (class "Default")
      (node (ref "DA1") (pin "18") (pinfunction "18_18") (pintype "passive"))
      (node (ref "R5P") (pin "2") (pinfunction "2_2") (pintype "passive"))
    )
    (net (code "137") (name "Net-(DD4A-DIR)") (class "Default")
      (node (ref "DD4") (pin "1") (pinfunction "DIR_1") (pintype "input"))
      (node (ref "R35") (pin "1") (pinfunction "1_1") (pintype "passive"))
    )
    (net (code "138") (name "Net-(DD5A-A1)") (class "Default")
      (node (ref "DD5") (pin "1") (pinfunction "DIR_1") (pintype "input"))
      (node (ref "DD5") (pin "2") (pinfunction "A1_2") (pintype "bidirectional"))
      (node (ref "DD5") (pin "3") (pinfunction "A2_3") (pintype "bidirectional"))
      (node (ref "R36") (pin "1") (pinfunction "1_1") (pintype "passive"))
    )
    (net (code "139") (name "Net-(DD10A-DIR)") (class "Default")
      (node (ref "DD10") (pin "1") (pinfunction "DIR_1") (pintype "input"))
      (node (ref "R37") (pin "1") (pinfunction "1_1") (pintype "passive"))
    )
    (net (code "140") (name "Net-(DD11A-I)") (class "Default")
      (node (ref "DD11") (pin "1") (pinfunction "I_1") (pintype "input"))
      (node (ref "R1") (pin "1") (pinfunction "1_1") (pintype "passive"))
      (node (ref "Z1") (pin "1") (pinfunction "1_1") (pintype "passive"))
    )
    (net (code "141") (name "Net-(DD11A-O)") (class "Default")
      (node (ref "DD11") (pin "2") (pinfunction "O_2") (pintype "output"))
      (node (ref "DD11") (pin "3") (pinfunction "I_3") (pintype "input"))
      (node (ref "R1") (pin "2") (pinfunction "2_2") (pintype "passive"))
      (node (ref "R2") (pin "1") (pinfunction "1_1") (pintype "passive"))
    )
    (net (code "142") (name "Net-(DD11B-O)") (class "Default")
      (node (ref "DD11") (pin "4") (pinfunction "O_4") (pintype "output"))
      (node (ref "DD11") (pin "5") (pinfunction "I_5") (pintype "input"))
      (node (ref "R2") (pin "2") (pinfunction "2_2") (pintype "passive"))
      (node (ref "Z1") (pin "2") (pinfunction "2_2") (pintype "passive"))
    )
    (net (code "143") (name "Net-(DD11D-I)") (class "Default")
      (node (ref "DD11") (pin "13") (pinfunction "I_13") (pintype "input"))
      (node (ref "R38") (pin "1") (pinfunction "1_1") (pintype "passive"))
      (node (ref "Z2") (pin "1") (pinfunction "1_1") (pintype "passive"))
    )
    (net (code "144") (name "Net-(DD11D-O)") (class "Default")
      (node (ref "DD11") (pin "11") (pinfunction "I_11") (pintype "input"))
      (node (ref "DD11") (pin "12") (pinfunction "O_12") (pintype "output"))
      (node (ref "R38") (pin "2") (pinfunction "2_2") (pintype "passive"))
      (node (ref "R39") (pin "1") (pinfunction "1_1") (pintype "passive"))
    )
    (net (code "145") (name "Net-(DD11E-O)") (class "Default")
      (node (ref "DD11") (pin "10") (pinfunction "O_10") (pintype "output"))
      (node (ref "DD11") (pin "9") (pinfunction "I_9") (pintype "input"))
      (node (ref "R39") (pin "2") (pinfunction "2_2") (pintype "passive"))
      (node (ref "Z2") (pin "2") (pinfunction "2_2") (pintype "passive"))
    )
    (net (code "146") (name "Net-(DD12A-CLK)") (class "Default")
      (node (ref "DD12") (pin "1") (pinfunction "CLR_1") (pintype "input"))
      (node (ref "DD12") (pin "10") (pinfunction "PRE_10") (pintype "input"))
      (node (ref "DD12") (pin "13") (pinfunction "CLR_13") (pintype "input"))
      (node (ref "DD12") (pin "2") (pinfunction "D_2") (pintype "input"))
      (node (ref "DD12") (pin "3") (pinfunction "CLK_3") (pintype "input"))
      (node (ref "DD12") (pin "4") (pinfunction "PRE_4") (pintype "input"))
      (node (ref "R40") (pin "1") (pinfunction "1_1") (pintype "passive"))
    )
    (net (code "147") (name "Net-(DD12B-D)") (class "Default")
      (node (ref "DD12") (pin "12") (pinfunction "D_12") (pintype "input"))
      (node (ref "DD12") (pin "8") (pinfunction "~{Q}_8") (pintype "output"))
    )
    (net (code "148") (name "Net-(HL1-PadC)") (class "Default")
      (node (ref "HL1") (pin "C") (pinfunction "C_C") (pintype "passive"))
      (node (ref "R34") (pin "2") (pinfunction "2_2") (pintype "passive"))
    )
    (net (code "149") (name "Net-(HL2-PadC)") (class "Default")
      (node (ref "HL2") (pin "C") (pinfunction "C_C") (pintype "passive"))
      (node (ref "R33") (pin "2") (pinfunction "2_2") (pintype "passive"))
    )
    (net (code "150") (name "Net-(JP1-Pad2)") (class "Default")
      (node (ref "JP1") (pin "2") (pinfunction "2_2") (pintype "passive"))
      (node (ref "R9P") (pin "1") (pinfunction "1_1") (pintype "passive"))
    )
    (net (code "151") (name "Net-(JP2-Pad2)") (class "Default")
      (node (ref "JP2") (pin "2") (pinfunction "2_2") (pintype "passive"))
      (node (ref "R8P") (pin "1") (pinfunction "1_1") (pintype "passive"))
    )
    (net (code "152") (name "Net-(R17-Pad1)") (class "Default")
      (node (ref "R17") (pin "1") (pinfunction "1_1") (pintype "passive"))
      (node (ref "R18") (pin "2") (pinfunction "2_2") (pintype "passive"))
      (node (ref "VT1") (pin "B") (pinfunction "B_B") (pintype "passive"))
    )
    (net (code "153") (name "Net-(R_B-E)") (class "Default")
      (node (ref "R5") (pin "2") (pinfunction "2_2") (pintype "passive"))
      (node (ref "R8") (pin "2") (pinfunction "2_2") (pintype "passive"))
      (node (ref "R_B") (pin "1") (pinfunction "E_1") (pintype "passive"))
    )
    (net (code "154") (name "Net-(R_B-S)") (class "Default")
      (node (ref "C2P") (pin "1") (pinfunction "1_1") (pintype "passive"))
      (node (ref "R_B") (pin "2") (pinfunction "S_2") (pintype "passive"))
    )
    (net (code "155") (name "Net-(R_G-E)") (class "Default")
      (node (ref "R6") (pin "2") (pinfunction "2_2") (pintype "passive"))
      (node (ref "R9") (pin "2") (pinfunction "2_2") (pintype "passive"))
      (node (ref "R_G") (pin "1") (pinfunction "E_1") (pintype "passive"))
    )
    (net (code "156") (name "Net-(R_G-S)") (class "Default")
      (node (ref "C3P") (pin "1") (pinfunction "1_1") (pintype "passive"))
      (node (ref "R_G") (pin "2") (pinfunction "S_2") (pintype "passive"))
    )
    (net (code "157") (name "Net-(R_R-E)") (class "Default")
      (node (ref "R10") (pin "2") (pinfunction "2_2") (pintype "passive"))
      (node (ref "R7") (pin "2") (pinfunction "2_2") (pintype "passive"))
      (node (ref "R_R") (pin "1") (pinfunction "E_1") (pintype "passive"))
    )
    (net (code "158") (name "Net-(R_R-S)") (class "Default")
      (node (ref "C1P") (pin "1") (pinfunction "1_1") (pintype "passive"))
      (node (ref "R_R") (pin "2") (pinfunction "S_2") (pintype "passive"))
    )
    (net (code "159") (name "Net-(R_SY-E)") (class "Default")
      (node (ref "R4") (pin "2") (pinfunction "2_2") (pintype "passive"))
      (node (ref "R_SY") (pin "1") (pinfunction "E_1") (pintype "passive"))
    )
    (net (code "160") (name "Net-(R_SY-S)") (class "Default")
      (node (ref "DA1") (pin "10") (pinfunction "10_10") (pintype "passive"))
      (node (ref "R_SY") (pin "2") (pinfunction "S_2") (pintype "passive"))
    )
    (net (code "161") (name "Net-(X4-CD{slash}DAT3{slash}CS)") (class "Default")
      (node (ref "R16") (pin "1") (pinfunction "1_1") (pintype "passive"))
      (node (ref "R33") (pin "1") (pinfunction "1_1") (pintype "passive"))
      (node (ref "VT1") (pin "C") (pinfunction "C_C") (pintype "passive"))
      (node (ref "X4") (pin "1") (pinfunction "CD/DAT3/CS_1") (pintype "bidirectional"))
    )
    (net (code "162") (name "Net-(X4-CLK{slash}SCLK)") (class "Default")
      (node (ref "R12") (pin "2") (pinfunction "2_2") (pintype "passive"))
      (node (ref "R13") (pin "1") (pinfunction "1_1") (pintype "passive"))
      (node (ref "X4") (pin "5") (pinfunction "CLK/SCLK_5") (pintype "bidirectional"))
    )
    (net (code "163") (name "Net-(X4-CMD{slash}DI)") (class "Default")
      (node (ref "R14") (pin "2") (pinfunction "2_2") (pintype "passive"))
      (node (ref "R15") (pin "1") (pinfunction "1_1") (pintype "passive"))
      (node (ref "X4") (pin "2") (pinfunction "CMD/DI_2") (pintype "bidirectional"))
    )
    (net (code "164") (name "unconnected-(DA1-Pad5)") (class "Default")
      (node (ref "DA1") (pin "5") (pinfunction "5_5") (pintype "passive"))
    )
    (net (code "165") (name "unconnected-(DA1-Pad8)") (class "Default")
      (node (ref "DA1") (pin "8") (pinfunction "8_8") (pintype "passive"))
    )
    (net (code "166") (name "unconnected-(DA1-Pad11)") (class "Default")
      (node (ref "DA1") (pin "11") (pinfunction "11_11") (pintype "passive"))
    )
    (net (code "167") (name "unconnected-(DA1-Pad17)") (class "Default")
      (node (ref "DA1") (pin "17") (pinfunction "17_17") (pintype "passive"))
    )
    (net (code "168") (name "unconnected-(DD1-BUSAK-Pad23)") (class "Default")
      (node (ref "DD1") (pin "23") (pinfunction "BUSAK_23") (pintype "output"))
    )
    (net (code "169") (name "unconnected-(DD1-HALT-Pad18)") (class "Default")
      (node (ref "DD1") (pin "18") (pinfunction "HALT_18") (pintype "output"))
    )
    (net (code "170") (name "unconnected-(DD1-RFSH-Pad28)") (class "Default")
      (node (ref "DD1") (pin "28") (pinfunction "RFSH_28") (pintype "output"))
    )
    (net (code "171") (name "unconnected-(DD2A-OE1-Pad84)") (class "Default")
      (node (ref "DD2") (pin "84") (pinfunction "OE1_84") (pintype "input"))
    )
    (net (code "172") (name "unconnected-(DD3A-NC-Pad1)") (class "Default")
      (node (ref "DD3") (pin "1") (pinfunction "NC_1") (pintype "no_connect"))
    )
    (net (code "173") (name "unconnected-(DD5A-B1-Pad18)") (class "Default")
      (node (ref "DD5") (pin "18") (pinfunction "B1_18") (pintype "bidirectional"))
    )
    (net (code "174") (name "unconnected-(DD5A-B2-Pad17)") (class "Default")
      (node (ref "DD5") (pin "17") (pinfunction "B2_17") (pintype "bidirectional"))
    )
    (net (code "175") (name "unconnected-(DD7-AREF-Pad32)") (class "Default")
      (node (ref "DD7") (pin "32") (pinfunction "AREF_32") (pintype "passive"))
    )
    (net (code "176") (name "unconnected-(DD7-XTAL2-Pad12)") (class "Default")
      (node (ref "DD7") (pin "12") (pinfunction "XTAL2_12") (pintype "bidirectional"))
    )
    (net (code "177") (name "unconnected-(DD9-IOA0-Pad21)") (class "Default")
      (node (ref "DD9") (pin "21") (pinfunction "IOA0_21") (pintype "bidirectional"))
    )
    (net (code "178") (name "unconnected-(DD9-IOA1-Pad20)") (class "Default")
      (node (ref "DD9") (pin "20") (pinfunction "IOA1_20") (pintype "bidirectional"))
    )
    (net (code "179") (name "unconnected-(DD9-IOA2-Pad19)") (class "Default")
      (node (ref "DD9") (pin "19") (pinfunction "IOA2_19") (pintype "bidirectional"))
    )
    (net (code "180") (name "unconnected-(DD9-IOA3-Pad18)") (class "Default")
      (node (ref "DD9") (pin "18") (pinfunction "IOA3_18") (pintype "bidirectional"))
    )
    (net (code "181") (name "unconnected-(DD9-IOA4-Pad17)") (class "Default")
      (node (ref "DD9") (pin "17") (pinfunction "IOA4_17") (pintype "bidirectional"))
    )
    (net (code "182") (name "unconnected-(DD9-IOA5-Pad16)") (class "Default")
      (node (ref "DD9") (pin "16") (pinfunction "IOA5_16") (pintype "bidirectional"))
    )
    (net (code "183") (name "unconnected-(DD9-IOA6-Pad15)") (class "Default")
      (node (ref "DD9") (pin "15") (pinfunction "IOA6_15") (pintype "bidirectional"))
    )
    (net (code "184") (name "unconnected-(DD9-IOA7-Pad14)") (class "Default")
      (node (ref "DD9") (pin "14") (pinfunction "IOA7_14") (pintype "bidirectional"))
    )
    (net (code "185") (name "unconnected-(DD9-IOB0-Pad13)") (class "Default")
      (node (ref "DD9") (pin "13") (pinfunction "IOB0_13") (pintype "bidirectional"))
    )
    (net (code "186") (name "unconnected-(DD9-IOB1-Pad12)") (class "Default")
      (node (ref "DD9") (pin "12") (pinfunction "IOB1_12") (pintype "bidirectional"))
    )
    (net (code "187") (name "unconnected-(DD9-IOB2-Pad11)") (class "Default")
      (node (ref "DD9") (pin "11") (pinfunction "IOB2_11") (pintype "bidirectional"))
    )
    (net (code "188") (name "unconnected-(DD9-IOB3-Pad10)") (class "Default")
      (node (ref "DD9") (pin "10") (pinfunction "IOB3_10") (pintype "bidirectional"))
    )
    (net (code "189") (name "unconnected-(DD9-IOB4-Pad9)") (class "Default")
      (node (ref "DD9") (pin "9") (pinfunction "IOB4_9") (pintype "bidirectional"))
    )
    (net (code "190") (name "unconnected-(DD9-IOB5-Pad8)") (class "Default")
      (node (ref "DD9") (pin "8") (pinfunction "IOB5_8") (pintype "bidirectional"))
    )
    (net (code "191") (name "unconnected-(DD9-IOB6-Pad7)") (class "Default")
      (node (ref "DD9") (pin "7") (pinfunction "IOB6_7") (pintype "bidirectional"))
    )
    (net (code "192") (name "unconnected-(DD9-IOB7-Pad6)") (class "Default")
      (node (ref "DD9") (pin "6") (pinfunction "IOB7_6") (pintype "bidirectional"))
    )
    (net (code "193") (name "unconnected-(DD9-MOD-Pad26)") (class "Default")
      (node (ref "DD9") (pin "26") (pinfunction "MOD_26") (pintype "bidirectional"))
    )
    (net (code "194") (name "unconnected-(DD9-TEST1-Pad39)") (class "Default")
      (node (ref "DD9") (pin "39") (pinfunction "TEST1_39") (pintype "bidirectional"))
    )
    (net (code "195") (name "unconnected-(DD12A-Q-Pad5)") (class "Default")
      (node (ref "DD12") (pin "5") (pinfunction "Q_5") (pintype "output"))
    )
    (net (code "196") (name "unconnected-(DD12A-~{Q}-Pad6)") (class "Default")
      (node (ref "DD12") (pin "6") (pinfunction "~{Q}_6") (pintype "output"))
    )
    (net (code "197") (name "unconnected-(X2-Pad2)") (class "Default")
      (node (ref "X2") (pin "2") (pinfunction "2_2") (pintype "passive"))
    )
    (net (code "198") (name "unconnected-(X2-Pad6)") (class "Default")
      (node (ref "X2") (pin "6") (pinfunction "6_6") (pintype "passive"))
    )
    (net (code "199") (name "unconnected-(X2-Pad8)") (class "Default")
      (node (ref "X2") (pin "8") (pinfunction "8_8") (pintype "passive"))
    )
    (net (code "200") (name "unconnected-(X2-Pad10)") (class "Default")
      (node (ref "X2") (pin "10") (pinfunction "10_10") (pintype "passive"))
    )
    (net (code "201") (name "unconnected-(X2-Pad12)") (class "Default")
      (node (ref "X2") (pin "12") (pinfunction "12_12") (pintype "passive"))
    )
    (net (code "202") (name "unconnected-(X2-Pad16)") (class "Default")
      (node (ref "X2") (pin "16") (pinfunction "16_16") (pintype "passive"))
    )
    (net (code "203") (name "unconnected-(X2-Pad20)") (class "Default")
      (node (ref "X2") (pin "20") (pinfunction "20_20") (pintype "passive"))
    )
    (net (code "204") (name "unconnected-(X3-Pad2)") (class "Default")
      (node (ref "X3") (pin "2") (pinfunction "2_2") (pintype "passive"))
    )
    (net (code "205") (name "unconnected-(X3-Pad6)") (class "Default")
      (node (ref "X3") (pin "6") (pinfunction "6_6") (pintype "passive"))
    )
    (net (code "206") (name "unconnected-(X4-CDI#-Pad10)") (class "Default")
      (node (ref "X4") (pin "10") (pinfunction "CDI#_10") (pintype "output"))
    )
    (net (code "207") (name "unconnected-(X4-DAT1-Pad8)") (class "Default")
      (node (ref "X4") (pin "8") (pinfunction "DAT1_8") (pintype "bidirectional"))
    )
    (net (code "208") (name "unconnected-(X4-DAT2-Pad9)") (class "Default")
      (node (ref "X4") (pin "9") (pinfunction "DAT2_9") (pintype "bidirectional"))
    )
    (net (code "209") (name "unconnected-(X4-WP-Pad11)") (class "Default")
      (node (ref "X4") (pin "11") (pinfunction "WP_11") (pintype "output"))
    )
    (net (code "210") (name "unconnected-(X5-Pad7)") (class "Default")
      (node (ref "X5") (pin "7") (pinfunction "7_7") (pintype "passive"))
    )
    (net (code "211") (name "unconnected-(X5-Pad8)") (class "Default")
      (node (ref "X5") (pin "8") (pinfunction "8_8") (pintype "passive"))
    )
  )
)
